# AtoVproject_16n_BOURNS_V1_2NL.net
KiCad netlist of a schematic drawn in EAGLE
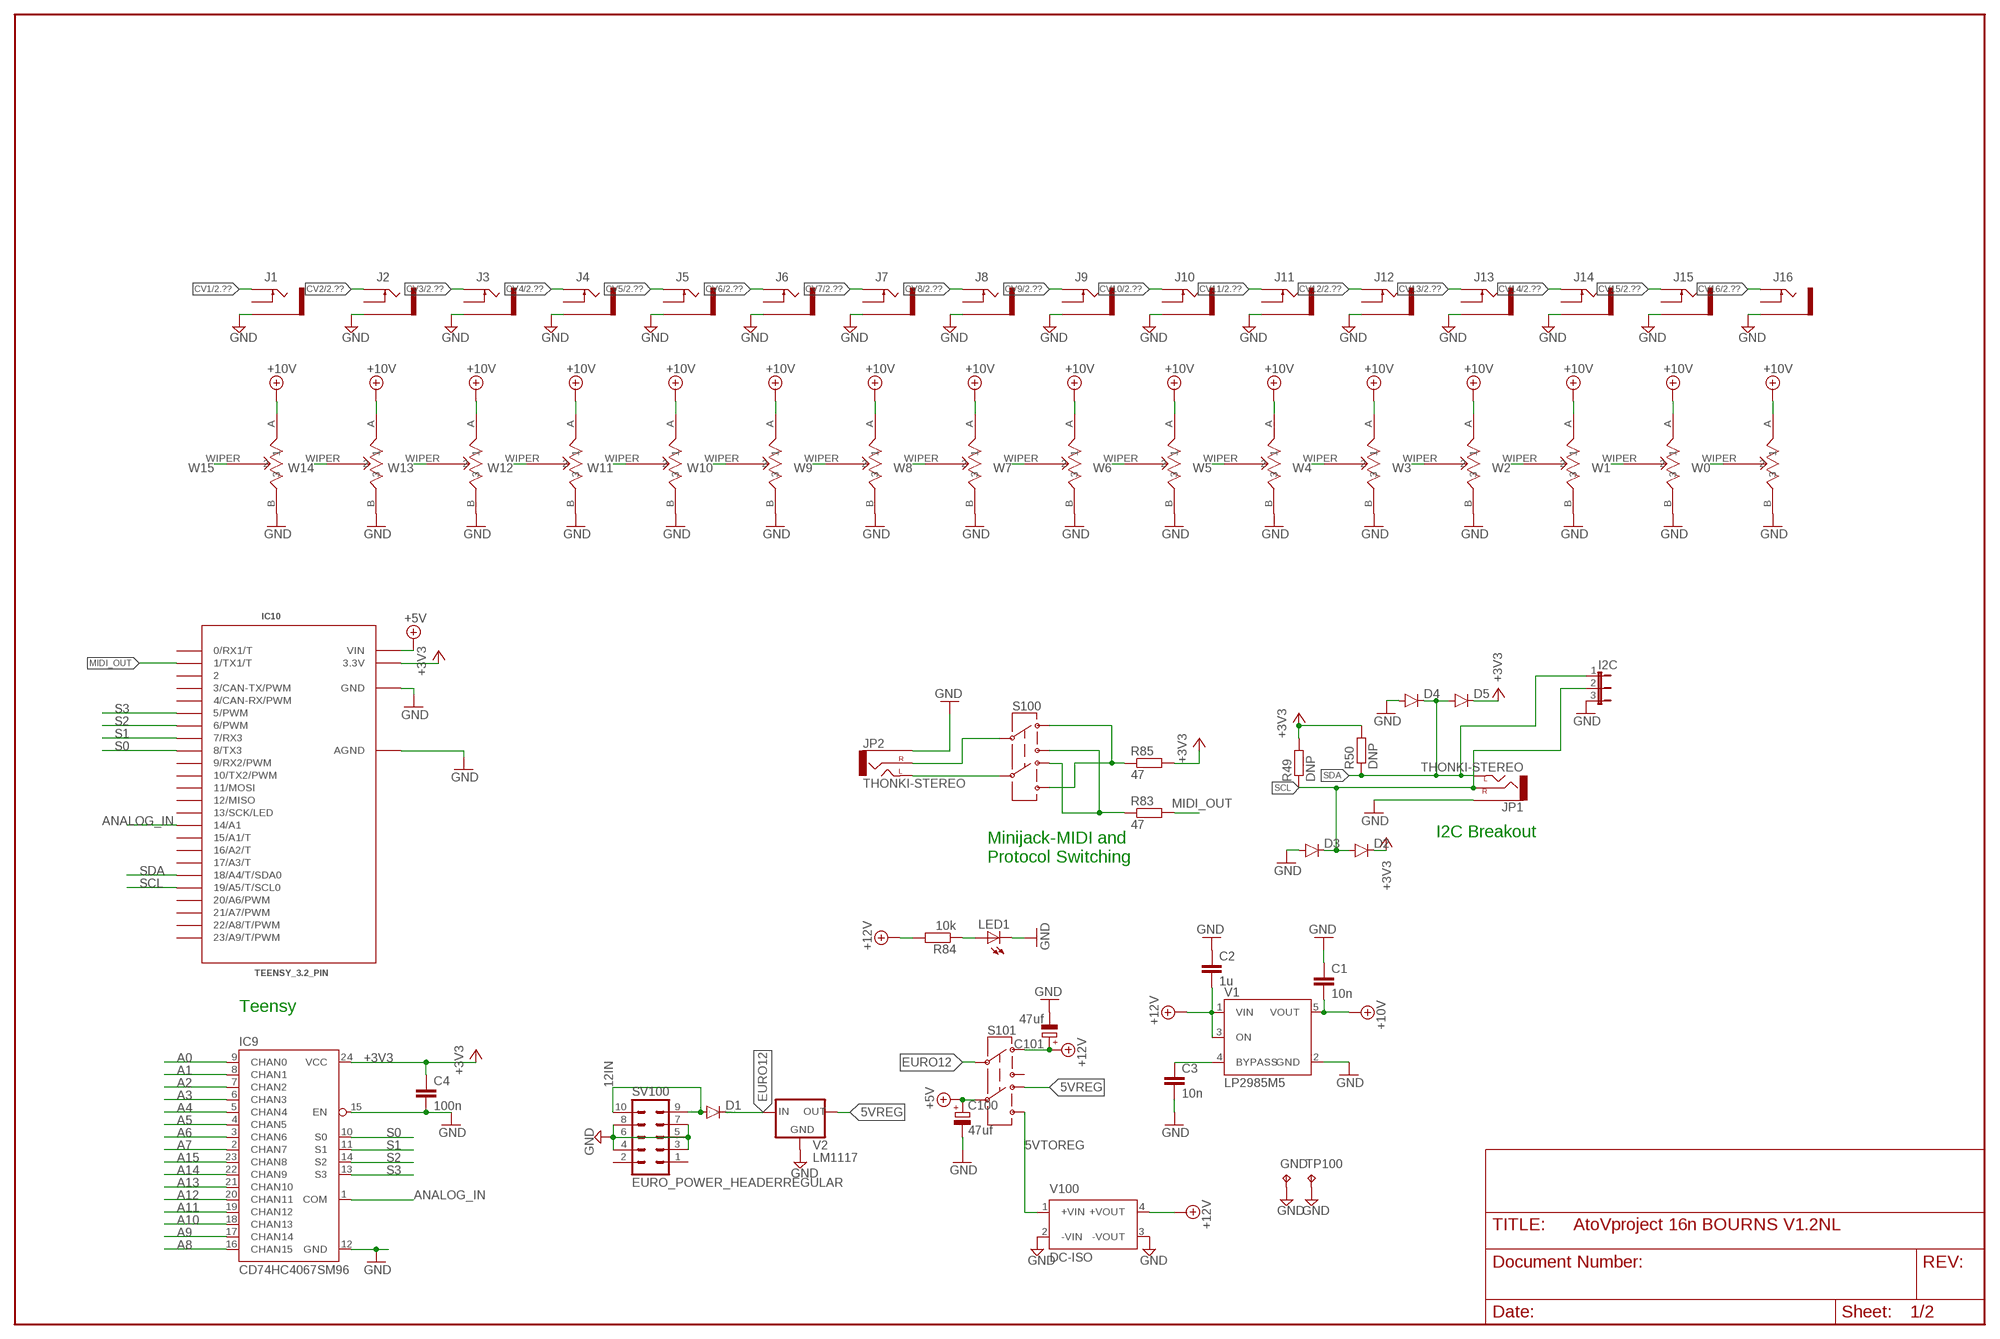
[diagram p0: schematic, sheet 1]
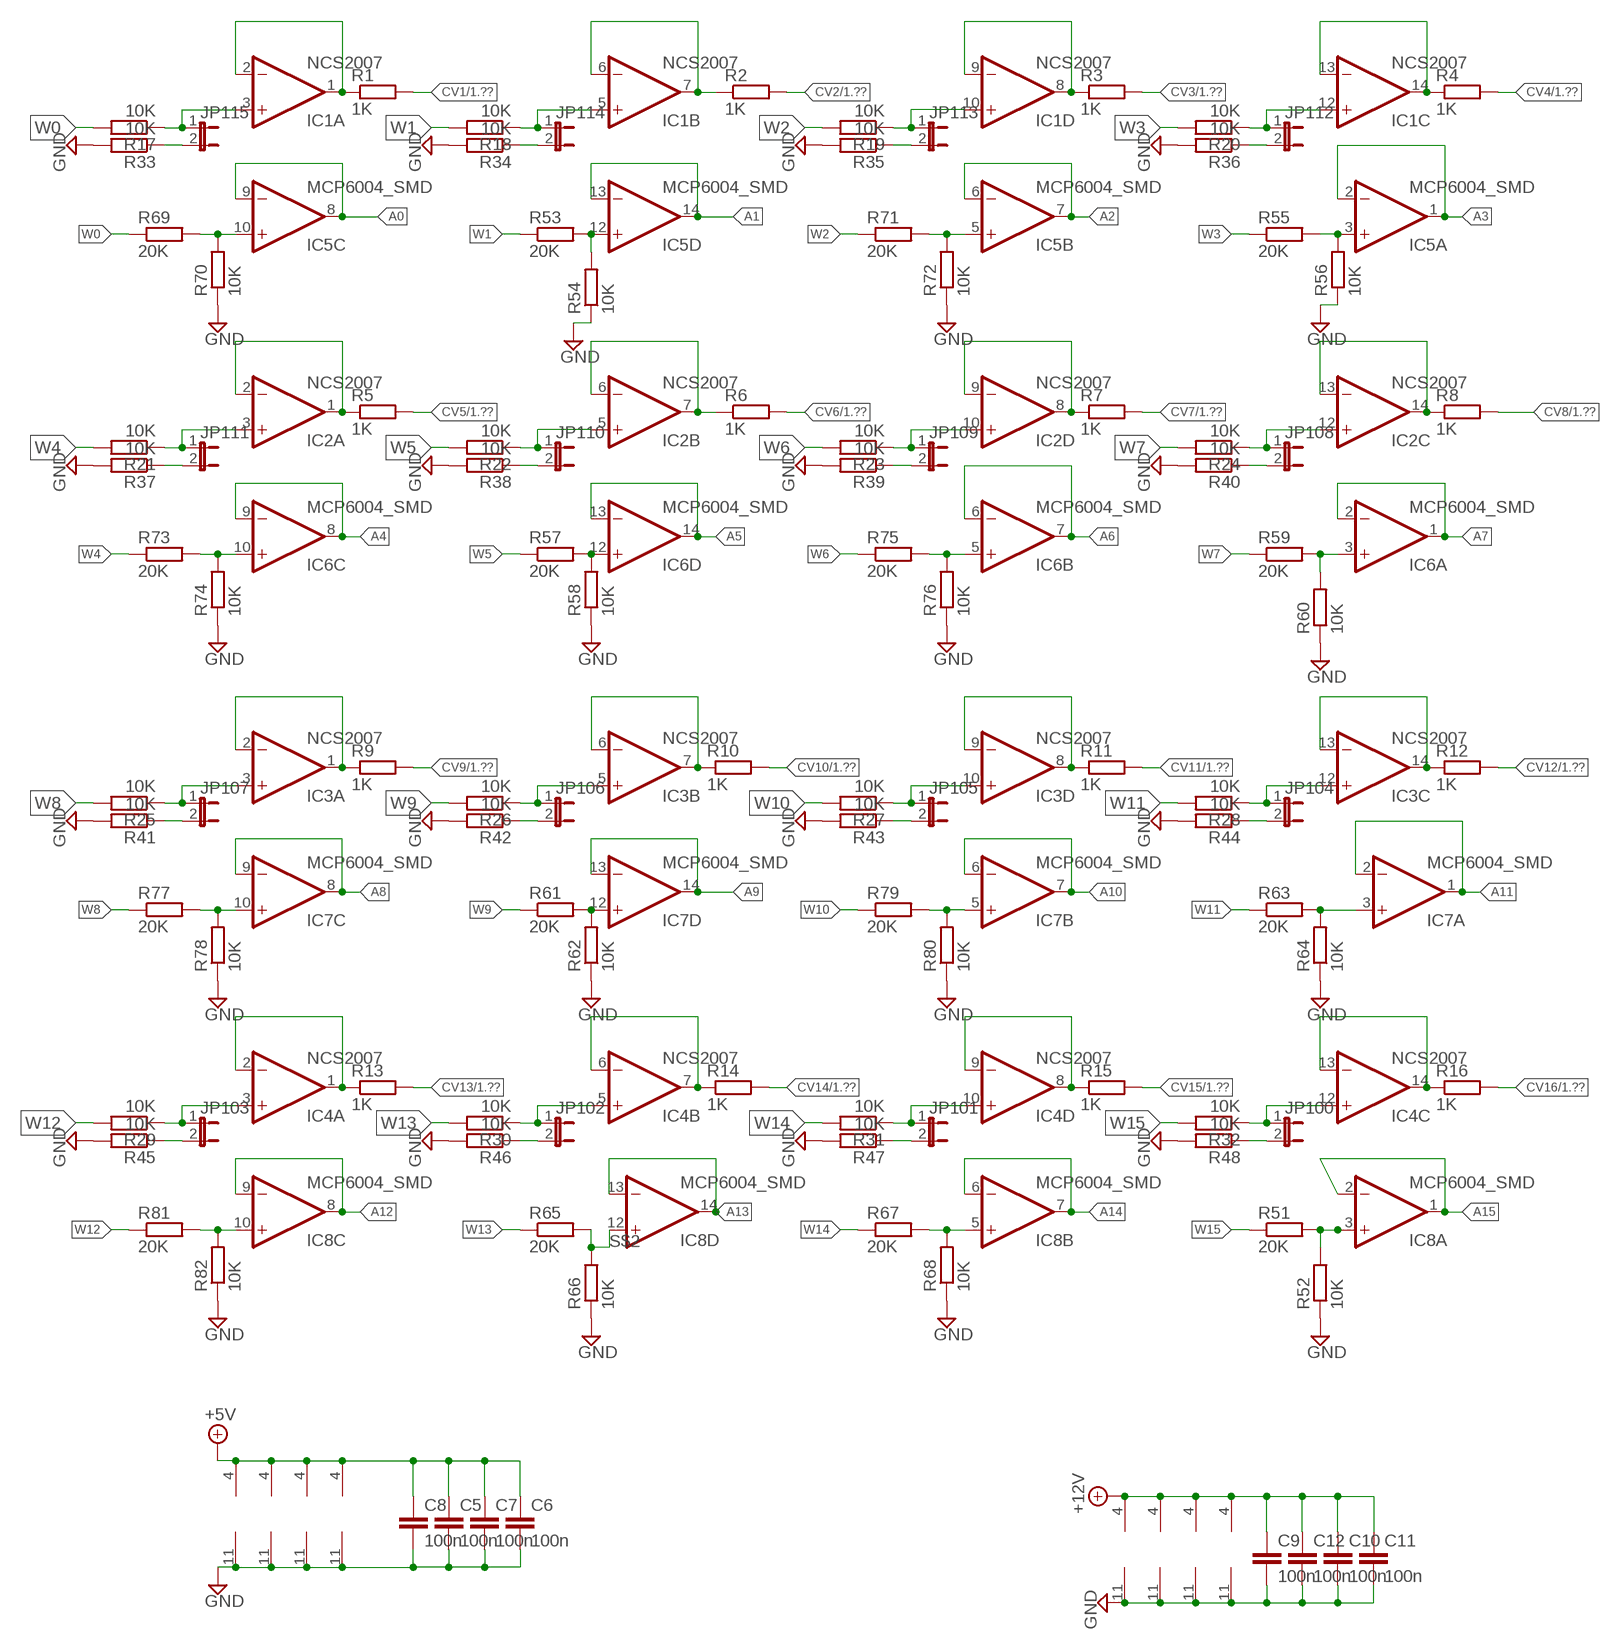
[diagram p1: schematic, sheet 2]

(export (version "E")
  (design (tool "Eeschema 10.0.6"))
  (components
    (comp (ref "C5")
      (value "100n")
      (footprint "eagle-import:C0805")
      (libsource (lib "eagle-import") (part "C-EUC0805"))
    )
    (comp (ref "C6")
      (value "100n")
      (footprint "eagle-import:C0805")
      (libsource (lib "eagle-import") (part "C-EUC0805"))
    )
    (comp (ref "C7")
      (value "100n")
      (footprint "eagle-import:C0805")
      (libsource (lib "eagle-import") (part "C-EUC0805"))
    )
    (comp (ref "C8")
      (value "100n")
      (footprint "eagle-import:C0805")
      (libsource (lib "eagle-import") (part "C-EUC0805"))
    )
    (comp (ref "C9")
      (value "100n")
      (footprint "eagle-import:C0805")
      (libsource (lib "eagle-import") (part "C-EUC0805"))
    )
    (comp (ref "C10")
      (value "100n")
      (footprint "eagle-import:C0805")
      (libsource (lib "eagle-import") (part "C-EUC0805"))
    )
    (comp (ref "C11")
      (value "100n")
      (footprint "eagle-import:C0805")
      (libsource (lib "eagle-import") (part "C-EUC0805"))
    )
    (comp (ref "C12")
      (value "100n")
      (footprint "eagle-import:C0805")
      (libsource (lib "eagle-import") (part "C-EUC0805"))
    )
    (comp (ref "IC1")
      (value "NCS2007")
      (footprint "eagle-import:SO14")
      (libsource (lib "eagle-import") (part "TL074"))
    )
    (comp (ref "IC2")
      (value "NCS2007")
      (footprint "eagle-import:SO14")
      (libsource (lib "eagle-import") (part "TL074"))
    )
    (comp (ref "IC3")
      (value "NCS2007")
      (footprint "eagle-import:SO14")
      (libsource (lib "eagle-import") (part "TL074"))
    )
    (comp (ref "IC4")
      (value "NCS2007")
      (footprint "eagle-import:SO14")
      (libsource (lib "eagle-import") (part "TL074"))
    )
    (comp (ref "IC5")
      (value "MCP6004_SMD")
      (footprint "eagle-import:SO14")
      (libsource (lib "eagle-import") (part "MCP6004_SMD"))
    )
    (comp (ref "IC6")
      (value "MCP6004_SMD")
      (footprint "eagle-import:SO14")
      (libsource (lib "eagle-import") (part "MCP6004_SMD"))
    )
    (comp (ref "IC7")
      (value "MCP6004_SMD")
      (footprint "eagle-import:SO14")
      (libsource (lib "eagle-import") (part "MCP6004_SMD"))
    )
    (comp (ref "IC8")
      (value "MCP6004_SMD")
      (footprint "eagle-import:SO14")
      (libsource (lib "eagle-import") (part "MCP6004_SMD"))
    )
    (comp (ref "JP100")
      (value "JP1E3D")
      (footprint "eagle-import:1X02")
      (libsource (lib "eagle-import") (part "JP1E3D"))
    )
    (comp (ref "JP101")
      (value "JP1E3D")
      (footprint "eagle-import:1X02")
      (libsource (lib "eagle-import") (part "JP1E3D"))
    )
    (comp (ref "JP102")
      (value "JP1E3D")
      (footprint "eagle-import:1X02")
      (libsource (lib "eagle-import") (part "JP1E3D"))
    )
    (comp (ref "JP103")
      (value "JP1E3D")
      (footprint "eagle-import:1X02")
      (libsource (lib "eagle-import") (part "JP1E3D"))
    )
    (comp (ref "JP104")
      (value "JP1E3D")
      (footprint "eagle-import:1X02")
      (libsource (lib "eagle-import") (part "JP1E3D"))
    )
    (comp (ref "JP105")
      (value "JP1E3D")
      (footprint "eagle-import:1X02")
      (libsource (lib "eagle-import") (part "JP1E3D"))
    )
    (comp (ref "JP106")
      (value "JP1E3D")
      (footprint "eagle-import:1X02")
      (libsource (lib "eagle-import") (part "JP1E3D"))
    )
    (comp (ref "JP107")
      (value "JP1E3D")
      (footprint "eagle-import:1X02")
      (libsource (lib "eagle-import") (part "JP1E3D"))
    )
    (comp (ref "JP108")
      (value "JP1E3D")
      (footprint "eagle-import:1X02")
      (libsource (lib "eagle-import") (part "JP1E3D"))
    )
    (comp (ref "JP109")
      (value "JP1E3D")
      (footprint "eagle-import:1X02")
      (libsource (lib "eagle-import") (part "JP1E3D"))
    )
    (comp (ref "JP110")
      (value "JP1E3D")
      (footprint "eagle-import:1X02")
      (libsource (lib "eagle-import") (part "JP1E3D"))
    )
    (comp (ref "JP111")
      (value "JP1E3D")
      (footprint "eagle-import:1X02")
      (libsource (lib "eagle-import") (part "JP1E3D"))
    )
    (comp (ref "JP112")
      (value "JP1E3D")
      (footprint "eagle-import:1X02")
      (libsource (lib "eagle-import") (part "JP1E3D"))
    )
    (comp (ref "JP113")
      (value "JP1E3D")
      (footprint "eagle-import:1X02")
      (libsource (lib "eagle-import") (part "JP1E3D"))
    )
    (comp (ref "JP114")
      (value "JP1E3D")
      (footprint "eagle-import:1X02")
      (libsource (lib "eagle-import") (part "JP1E3D"))
    )
    (comp (ref "JP115")
      (value "JP1E3D")
      (footprint "eagle-import:1X02")
      (libsource (lib "eagle-import") (part "JP1E3D"))
    )
    (comp (ref "R1")
      (value "1K")
      (footprint "eagle-import:R0805")
      (libsource (lib "eagle-import") (part "R-EU_R0805"))
    )
    (comp (ref "R2")
      (value "1K")
      (footprint "eagle-import:R0805")
      (libsource (lib "eagle-import") (part "R-EU_R0805"))
    )
    (comp (ref "R3")
      (value "1K")
      (footprint "eagle-import:R0805")
      (libsource (lib "eagle-import") (part "R-EU_R0805"))
    )
    (comp (ref "R4")
      (value "1K")
      (footprint "eagle-import:R0805")
      (libsource (lib "eagle-import") (part "R-EU_R0805"))
    )
    (comp (ref "R5")
      (value "1K")
      (footprint "eagle-import:R0805")
      (libsource (lib "eagle-import") (part "R-EU_R0805"))
    )
    (comp (ref "R6")
      (value "1K")
      (footprint "eagle-import:R0805")
      (libsource (lib "eagle-import") (part "R-EU_R0805"))
    )
    (comp (ref "R7")
      (value "1K")
      (footprint "eagle-import:R0805")
      (libsource (lib "eagle-import") (part "R-EU_R0805"))
    )
    (comp (ref "R8")
      (value "1K")
      (footprint "eagle-import:R0805")
      (libsource (lib "eagle-import") (part "R-EU_R0805"))
    )
    (comp (ref "R9")
      (value "1K")
      (footprint "eagle-import:R0805")
      (libsource (lib "eagle-import") (part "R-EU_R0805"))
    )
    (comp (ref "R10")
      (value "1K")
      (footprint "eagle-import:R0805")
      (libsource (lib "eagle-import") (part "R-EU_R0805"))
    )
    (comp (ref "R11")
      (value "1K")
      (footprint "eagle-import:R0805")
      (libsource (lib "eagle-import") (part "R-EU_R0805"))
    )
    (comp (ref "R12")
      (value "1K")
      (footprint "eagle-import:R0805")
      (libsource (lib "eagle-import") (part "R-EU_R0805"))
    )
    (comp (ref "R13")
      (value "1K")
      (footprint "eagle-import:R0805")
      (libsource (lib "eagle-import") (part "R-EU_R0805"))
    )
    (comp (ref "R14")
      (value "1K")
      (footprint "eagle-import:R0805")
      (libsource (lib "eagle-import") (part "R-EU_R0805"))
    )
    (comp (ref "R15")
      (value "1K")
      (footprint "eagle-import:R0805")
      (libsource (lib "eagle-import") (part "R-EU_R0805"))
    )
    (comp (ref "R16")
      (value "1K")
      (footprint "eagle-import:R0805")
      (libsource (lib "eagle-import") (part "R-EU_R0805"))
    )
    (comp (ref "R17")
      (value "10K")
      (footprint "eagle-import:R0805")
      (libsource (lib "eagle-import") (part "R-EU_R0805"))
    )
    (comp (ref "R18")
      (value "10K")
      (footprint "eagle-import:R0805")
      (libsource (lib "eagle-import") (part "R-EU_R0805"))
    )
    (comp (ref "R19")
      (value "10K")
      (footprint "eagle-import:R0805")
      (libsource (lib "eagle-import") (part "R-EU_R0805"))
    )
    (comp (ref "R20")
      (value "10K")
      (footprint "eagle-import:R0805")
      (libsource (lib "eagle-import") (part "R-EU_R0805"))
    )
    (comp (ref "R21")
      (value "10K")
      (footprint "eagle-import:R0805")
      (libsource (lib "eagle-import") (part "R-EU_R0805"))
    )
    (comp (ref "R22")
      (value "10K")
      (footprint "eagle-import:R0805")
      (libsource (lib "eagle-import") (part "R-EU_R0805"))
    )
    (comp (ref "R23")
      (value "10K")
      (footprint "eagle-import:R0805")
      (libsource (lib "eagle-import") (part "R-EU_R0805"))
    )
    (comp (ref "R24")
      (value "10K")
      (footprint "eagle-import:R0805")
      (libsource (lib "eagle-import") (part "R-EU_R0805"))
    )
    (comp (ref "R25")
      (value "10K")
      (footprint "eagle-import:R0805")
      (libsource (lib "eagle-import") (part "R-EU_R0805"))
    )
    (comp (ref "R26")
      (value "10K")
      (footprint "eagle-import:R0805")
      (libsource (lib "eagle-import") (part "R-EU_R0805"))
    )
    (comp (ref "R27")
      (value "10K")
      (footprint "eagle-import:R0805")
      (libsource (lib "eagle-import") (part "R-EU_R0805"))
    )
    (comp (ref "R28")
      (value "10K")
      (footprint "eagle-import:R0805")
      (libsource (lib "eagle-import") (part "R-EU_R0805"))
    )
    (comp (ref "R29")
      (value "10K")
      (footprint "eagle-import:R0805")
      (libsource (lib "eagle-import") (part "R-EU_R0805"))
    )
    (comp (ref "R30")
      (value "10K")
      (footprint "eagle-import:R0805")
      (libsource (lib "eagle-import") (part "R-EU_R0805"))
    )
    (comp (ref "R31")
      (value "10K")
      (footprint "eagle-import:R0805")
      (libsource (lib "eagle-import") (part "R-EU_R0805"))
    )
    (comp (ref "R32")
      (value "10K")
      (footprint "eagle-import:R0805")
      (libsource (lib "eagle-import") (part "R-EU_R0805"))
    )
    (comp (ref "R33")
      (value "10K")
      (footprint "eagle-import:R0805")
      (libsource (lib "eagle-import") (part "R-EU_R0805"))
    )
    (comp (ref "R34")
      (value "10K")
      (footprint "eagle-import:R0805")
      (libsource (lib "eagle-import") (part "R-EU_R0805"))
    )
    (comp (ref "R35")
      (value "10K")
      (footprint "eagle-import:R0805")
      (libsource (lib "eagle-import") (part "R-EU_R0805"))
    )
    (comp (ref "R36")
      (value "10K")
      (footprint "eagle-import:R0805")
      (libsource (lib "eagle-import") (part "R-EU_R0805"))
    )
    (comp (ref "R37")
      (value "10K")
      (footprint "eagle-import:R0805")
      (libsource (lib "eagle-import") (part "R-EU_R0805"))
    )
    (comp (ref "R38")
      (value "10K")
      (footprint "eagle-import:R0805")
      (libsource (lib "eagle-import") (part "R-EU_R0805"))
    )
    (comp (ref "R39")
      (value "10K")
      (footprint "eagle-import:R0805")
      (libsource (lib "eagle-import") (part "R-EU_R0805"))
    )
    (comp (ref "R40")
      (value "10K")
      (footprint "eagle-import:R0805")
      (libsource (lib "eagle-import") (part "R-EU_R0805"))
    )
    (comp (ref "R41")
      (value "10K")
      (footprint "eagle-import:R0805")
      (libsource (lib "eagle-import") (part "R-EU_R0805"))
    )
    (comp (ref "R42")
      (value "10K")
      (footprint "eagle-import:R0805")
      (libsource (lib "eagle-import") (part "R-EU_R0805"))
    )
    (comp (ref "R43")
      (value "10K")
      (footprint "eagle-import:R0805")
      (libsource (lib "eagle-import") (part "R-EU_R0805"))
    )
    (comp (ref "R44")
      (value "10K")
      (footprint "eagle-import:R0805")
      (libsource (lib "eagle-import") (part "R-EU_R0805"))
    )
    (comp (ref "R45")
      (value "10K")
      (footprint "eagle-import:R0805")
      (libsource (lib "eagle-import") (part "R-EU_R0805"))
    )
    (comp (ref "R46")
      (value "10K")
      (footprint "eagle-import:R0805")
      (libsource (lib "eagle-import") (part "R-EU_R0805"))
    )
    (comp (ref "R47")
      (value "10K")
      (footprint "eagle-import:R0805")
      (libsource (lib "eagle-import") (part "R-EU_R0805"))
    )
    (comp (ref "R48")
      (value "10K")
      (footprint "eagle-import:R0805")
      (libsource (lib "eagle-import") (part "R-EU_R0805"))
    )
    (comp (ref "R51")
      (value "20K")
      (footprint "eagle-import:R0805")
      (libsource (lib "eagle-import") (part "R-EU_R0805"))
    )
    (comp (ref "R52")
      (value "10K")
      (footprint "eagle-import:R0805")
      (libsource (lib "eagle-import") (part "R-EU_R0805"))
    )
    (comp (ref "R53")
      (value "20K")
      (footprint "eagle-import:R0805")
      (libsource (lib "eagle-import") (part "R-EU_R0805"))
    )
    (comp (ref "R54")
      (value "10K")
      (footprint "eagle-import:R0805")
      (libsource (lib "eagle-import") (part "R-EU_R0805"))
    )
    (comp (ref "R55")
      (value "20K")
      (footprint "eagle-import:R0805")
      (libsource (lib "eagle-import") (part "R-EU_R0805"))
    )
    (comp (ref "R56")
      (value "10K")
      (footprint "eagle-import:R0805")
      (libsource (lib "eagle-import") (part "R-EU_R0805"))
    )
    (comp (ref "R57")
      (value "20K")
      (footprint "eagle-import:R0805")
      (libsource (lib "eagle-import") (part "R-EU_R0805"))
    )
    (comp (ref "R58")
      (value "10K")
      (footprint "eagle-import:R0805")
      (libsource (lib "eagle-import") (part "R-EU_R0805"))
    )
    (comp (ref "R59")
      (value "20K")
      (footprint "eagle-import:R0805")
      (libsource (lib "eagle-import") (part "R-EU_R0805"))
    )
    (comp (ref "R60")
      (value "10K")
      (footprint "eagle-import:R0805")
      (libsource (lib "eagle-import") (part "R-EU_R0805"))
    )
    (comp (ref "R61")
      (value "20K")
      (footprint "eagle-import:R0805")
      (libsource (lib "eagle-import") (part "R-EU_R0805"))
    )
    (comp (ref "R62")
      (value "10K")
      (footprint "eagle-import:R0805")
      (libsource (lib "eagle-import") (part "R-EU_R0805"))
    )
    (comp (ref "R63")
      (value "20K")
      (footprint "eagle-import:R0805")
      (libsource (lib "eagle-import") (part "R-EU_R0805"))
    )
    (comp (ref "R64")
      (value "10K")
      (footprint "eagle-import:R0805")
      (libsource (lib "eagle-import") (part "R-EU_R0805"))
    )
    (comp (ref "R65")
      (value "20K")
      (footprint "eagle-import:R0805")
      (libsource (lib "eagle-import") (part "R-EU_R0805"))
    )
    (comp (ref "R66")
      (value "10K")
      (footprint "eagle-import:R0805")
      (libsource (lib "eagle-import") (part "R-EU_R0805"))
    )
    (comp (ref "R67")
      (value "20K")
      (footprint "eagle-import:R0805")
      (libsource (lib "eagle-import") (part "R-EU_R0805"))
    )
    (comp (ref "R68")
      (value "10K")
      (footprint "eagle-import:R0805")
      (libsource (lib "eagle-import") (part "R-EU_R0805"))
    )
    (comp (ref "R69")
      (value "20K")
      (footprint "eagle-import:R0805")
      (libsource (lib "eagle-import") (part "R-EU_R0805"))
    )
    (comp (ref "R70")
      (value "10K")
      (footprint "eagle-import:R0805")
      (libsource (lib "eagle-import") (part "R-EU_R0805"))
    )
    (comp (ref "R71")
      (value "20K")
      (footprint "eagle-import:R0805")
      (libsource (lib "eagle-import") (part "R-EU_R0805"))
    )
    (comp (ref "R72")
      (value "10K")
      (footprint "eagle-import:R0805")
      (libsource (lib "eagle-import") (part "R-EU_R0805"))
    )
    (comp (ref "R73")
      (value "20K")
      (footprint "eagle-import:R0805")
      (libsource (lib "eagle-import") (part "R-EU_R0805"))
    )
    (comp (ref "R74")
      (value "10K")
      (footprint "eagle-import:R0805")
      (libsource (lib "eagle-import") (part "R-EU_R0805"))
    )
    (comp (ref "R75")
      (value "20K")
      (footprint "eagle-import:R0805")
      (libsource (lib "eagle-import") (part "R-EU_R0805"))
    )
    (comp (ref "R76")
      (value "10K")
      (footprint "eagle-import:R0805")
      (libsource (lib "eagle-import") (part "R-EU_R0805"))
    )
    (comp (ref "R77")
      (value "20K")
      (footprint "eagle-import:R0805")
      (libsource (lib "eagle-import") (part "R-EU_R0805"))
    )
    (comp (ref "R78")
      (value "10K")
      (footprint "eagle-import:R0805")
      (libsource (lib "eagle-import") (part "R-EU_R0805"))
    )
    (comp (ref "R79")
      (value "20K")
      (footprint "eagle-import:R0805")
      (libsource (lib "eagle-import") (part "R-EU_R0805"))
    )
    (comp (ref "R80")
      (value "10K")
      (footprint "eagle-import:R0805")
      (libsource (lib "eagle-import") (part "R-EU_R0805"))
    )
    (comp (ref "R81")
      (value "20K")
      (footprint "eagle-import:R0805")
      (libsource (lib "eagle-import") (part "R-EU_R0805"))
    )
    (comp (ref "R82")
      (value "10K")
      (footprint "eagle-import:R0805")
      (libsource (lib "eagle-import") (part "R-EU_R0805"))
    )
    (comp (ref "C1")
      (value "10n")
      (footprint "eagle-import:C0805")
      (libsource (lib "eagle-import") (part "C-EUC0805"))
    )
    (comp (ref "C2")
      (value "1u")
      (footprint "eagle-import:C0805")
      (libsource (lib "eagle-import") (part "C-EUC0805"))
    )
    (comp (ref "C3")
      (value "10n")
      (footprint "eagle-import:C0805")
      (libsource (lib "eagle-import") (part "C-EUC0805"))
    )
    (comp (ref "C4")
      (value "100n")
      (footprint "eagle-import:C0805")
      (libsource (lib "eagle-import") (part "C-EUC0805"))
    )
    (comp (ref "C100")
      (value "47uf")
      (footprint "eagle-import:E2,5-6")
      (libsource (lib "eagle-import") (part "CPOL-EUE2.5-6"))
    )
    (comp (ref "C101")
      (value "47uf")
      (footprint "eagle-import:E2,5-6")
      (libsource (lib "eagle-import") (part "CPOL-EUE2.5-6"))
    )
    (comp (ref "D1")
      (value "DIODE-SOD123")
      (footprint "eagle-import:SOD123")
      (libsource (lib "eagle-import") (part "DIODE-SOD123"))
    )
    (comp (ref "D2")
      (value "DIODESOD123")
      (footprint "eagle-import:SOD-123")
      (libsource (lib "eagle-import") (part "DIODESOD123"))
    )
    (comp (ref "D3")
      (value "DIODESOD123")
      (footprint "eagle-import:SOD-123")
      (libsource (lib "eagle-import") (part "DIODESOD123"))
    )
    (comp (ref "D4")
      (value "DIODESOD123")
      (footprint "eagle-import:SOD-123")
      (libsource (lib "eagle-import") (part "DIODESOD123"))
    )
    (comp (ref "D5")
      (value "DIODESOD123")
      (footprint "eagle-import:SOD-123")
      (libsource (lib "eagle-import") (part "DIODESOD123"))
    )
    (comp (ref "GND")
      (value "TPPAD1-17")
      (footprint "eagle-import:P1-17")
      (libsource (lib "eagle-import") (part "TPPAD1-17"))
    )
    (comp (ref "I2C")
      (value "JP2E")
      (footprint "eagle-import:JP2")
      (libsource (lib "eagle-import") (part "JP2E"))
    )
    (comp (ref "IC9")
      (value "CD74HC4067SM96")
      (footprint "eagle-import:SOIC127P1030X265-24")
      (libsource (lib "eagle-import") (part "744067SO24"))
    )
    (comp (ref "IC10")
      (value "TEENSY_3.2_PIN")
      (footprint "eagle-import:TEENSY_3_AND_LC_SERIES_BOARDS_V1.4_TEENSY_3.0-3.2&LC_DIL")
      (libsource (lib "eagle-import") (part "TEENSY_3.2_PIN"))
    )
    (comp (ref "J1")
      (value "THONKICONN")
      (footprint "eagle-import:WQP-PJ301M-12JACK-BANANA")
      (libsource (lib "eagle-import") (part "THONKICONN"))
    )
    (comp (ref "J2")
      (value "THONKICONN")
      (footprint "eagle-import:WQP-PJ301M-12JACK-BANANA")
      (libsource (lib "eagle-import") (part "THONKICONN"))
    )
    (comp (ref "J3")
      (value "THONKICONN")
      (footprint "eagle-import:WQP-PJ301M-12JACK-BANANA")
      (libsource (lib "eagle-import") (part "THONKICONN"))
    )
    (comp (ref "J4")
      (value "THONKICONN")
      (footprint "eagle-import:WQP-PJ301M-12JACK-BANANA")
      (libsource (lib "eagle-import") (part "THONKICONN"))
    )
    (comp (ref "J5")
      (value "THONKICONN")
      (footprint "eagle-import:WQP-PJ301M-12JACK-BANANA")
      (libsource (lib "eagle-import") (part "THONKICONN"))
    )
    (comp (ref "J6")
      (value "THONKICONN")
      (footprint "eagle-import:WQP-PJ301M-12JACK-BANANA")
      (libsource (lib "eagle-import") (part "THONKICONN"))
    )
    (comp (ref "J7")
      (value "THONKICONN")
      (footprint "eagle-import:WQP-PJ301M-12JACK-BANANA")
      (libsource (lib "eagle-import") (part "THONKICONN"))
    )
    (comp (ref "J8")
      (value "THONKICONN")
      (footprint "eagle-import:WQP-PJ301M-12JACK-BANANA")
      (libsource (lib "eagle-import") (part "THONKICONN"))
    )
    (comp (ref "J9")
      (value "THONKICONN")
      (footprint "eagle-import:WQP-PJ301M-12JACK-BANANA")
      (libsource (lib "eagle-import") (part "THONKICONN"))
    )
    (comp (ref "J10")
      (value "THONKICONN")
      (footprint "eagle-import:WQP-PJ301M-12JACK-BANANA")
      (libsource (lib "eagle-import") (part "THONKICONN"))
    )
    (comp (ref "J11")
      (value "THONKICONN")
      (footprint "eagle-import:WQP-PJ301M-12JACK-BANANA")
      (libsource (lib "eagle-import") (part "THONKICONN"))
    )
    (comp (ref "J12")
      (value "THONKICONN")
      (footprint "eagle-import:WQP-PJ301M-12JACK-BANANA")
      (libsource (lib "eagle-import") (part "THONKICONN"))
    )
    (comp (ref "J13")
      (value "THONKICONN")
      (footprint "eagle-import:WQP-PJ301M-12JACK-BANANA")
      (libsource (lib "eagle-import") (part "THONKICONN"))
    )
    (comp (ref "J14")
      (value "THONKICONN")
      (footprint "eagle-import:WQP-PJ301M-12JACK-BANANA")
      (libsource (lib "eagle-import") (part "THONKICONN"))
    )
    (comp (ref "J15")
      (value "THONKICONN")
      (footprint "eagle-import:WQP-PJ301M-12JACK-BANANA")
      (libsource (lib "eagle-import") (part "THONKICONN"))
    )
    (comp (ref "J16")
      (value "THONKICONN")
      (footprint "eagle-import:WQP-PJ301M-12JACK-BANANA")
      (libsource (lib "eagle-import") (part "THONKICONN"))
    )
    (comp (ref "JP1")
      (value "THONKI-STEREO")
      (footprint "eagle-import:WQP-PJ366ST_JACK")
      (libsource (lib "eagle-import") (part "THONKI-STEREO"))
    )
    (comp (ref "JP2")
      (value "THONKI-STEREO")
      (footprint "eagle-import:WQP-PJ366ST_JACK")
      (libsource (lib "eagle-import") (part "THONKI-STEREO"))
    )
    (comp (ref "LED1")
      (value "LED")
      (footprint "eagle-import:LED3MM")
      (libsource (lib "eagle-import") (part "LED"))
    )
    (comp (ref "R49")
      (value "DNP")
      (footprint "eagle-import:R0805")
      (libsource (lib "eagle-import") (part "R-EU_R0805"))
    )
    (comp (ref "R50")
      (value "DNP")
      (footprint "eagle-import:R0805")
      (libsource (lib "eagle-import") (part "R-EU_R0805"))
    )
    (comp (ref "R83")
      (value "47")
      (footprint "eagle-import:R0805")
      (libsource (lib "eagle-import") (part "R-EU_R0805"))
    )
    (comp (ref "R84")
      (value "10k")
      (footprint "eagle-import:R0805")
      (libsource (lib "eagle-import") (part "R-EU_R0805"))
    )
    (comp (ref "R85")
      (value "47")
      (footprint "eagle-import:R0805")
      (libsource (lib "eagle-import") (part "R-EU_R0805"))
    )
    (comp (ref "S100")
      (value "SWITCH-DPDTEG2211")
      (footprint "eagle-import:EG2211")
      (libsource (lib "eagle-import") (part "SWITCH-DPDTEG2211"))
    )
    (comp (ref "S101")
      (value "SWITCH-DPDTEG2211")
      (footprint "eagle-import:EG2211")
      (libsource (lib "eagle-import") (part "SWITCH-DPDTEG2211"))
    )
    (comp (ref "SV100")
      (value "EURO_POWER_HEADERREGULAR")
      (footprint "eagle-import:EURO_POWER_HEADER")
      (libsource (lib "eagle-import") (part "EURO_POWER_HEADERREGULAR"))
    )
    (comp (ref "TP100")
      (value "TPPAD1-17")
      (footprint "eagle-import:P1-17")
      (libsource (lib "eagle-import") (part "TPPAD1-17"))
    )
    (comp (ref "U$1")
      (value "SLIDERSBOURNS-60MM")
      (footprint "eagle-import:SLIDEPOT-75")
      (libsource (lib "eagle-import") (part "SLIDERSBOURNS-60MM"))
    )
    (comp (ref "U$2")
      (value "SLIDERSBOURNS-60MM")
      (footprint "eagle-import:SLIDEPOT-75")
      (libsource (lib "eagle-import") (part "SLIDERSBOURNS-60MM"))
    )
    (comp (ref "U$3")
      (value "SLIDERSBOURNS-60MM")
      (footprint "eagle-import:SLIDEPOT-75")
      (libsource (lib "eagle-import") (part "SLIDERSBOURNS-60MM"))
    )
    (comp (ref "U$4")
      (value "SLIDERSBOURNS-60MM")
      (footprint "eagle-import:SLIDEPOT-75")
      (libsource (lib "eagle-import") (part "SLIDERSBOURNS-60MM"))
    )
    (comp (ref "U$5")
      (value "SLIDERSBOURNS-60MM")
      (footprint "eagle-import:SLIDEPOT-75")
      (libsource (lib "eagle-import") (part "SLIDERSBOURNS-60MM"))
    )
    (comp (ref "U$6")
      (value "SLIDERSBOURNS-60MM")
      (footprint "eagle-import:SLIDEPOT-75")
      (libsource (lib "eagle-import") (part "SLIDERSBOURNS-60MM"))
    )
    (comp (ref "U$7")
      (value "SLIDERSBOURNS-60MM")
      (footprint "eagle-import:SLIDEPOT-75")
      (libsource (lib "eagle-import") (part "SLIDERSBOURNS-60MM"))
    )
    (comp (ref "U$8")
      (value "SLIDERSBOURNS-60MM")
      (footprint "eagle-import:SLIDEPOT-75")
      (libsource (lib "eagle-import") (part "SLIDERSBOURNS-60MM"))
    )
    (comp (ref "U$9")
      (value "SLIDERSBOURNS-60MM")
      (footprint "eagle-import:SLIDEPOT-75")
      (libsource (lib "eagle-import") (part "SLIDERSBOURNS-60MM"))
    )
    (comp (ref "U$10")
      (value "SLIDERSBOURNS-60MM")
      (footprint "eagle-import:SLIDEPOT-75")
      (libsource (lib "eagle-import") (part "SLIDERSBOURNS-60MM"))
    )
    (comp (ref "U$11")
      (value "SLIDERSBOURNS-60MM")
      (footprint "eagle-import:SLIDEPOT-75")
      (libsource (lib "eagle-import") (part "SLIDERSBOURNS-60MM"))
    )
    (comp (ref "U$12")
      (value "SLIDERSBOURNS-60MM")
      (footprint "eagle-import:SLIDEPOT-75")
      (libsource (lib "eagle-import") (part "SLIDERSBOURNS-60MM"))
    )
    (comp (ref "U$13")
      (value "SLIDERSBOURNS-60MM")
      (footprint "eagle-import:SLIDEPOT-75")
      (libsource (lib "eagle-import") (part "SLIDERSBOURNS-60MM"))
    )
    (comp (ref "U$14")
      (value "SLIDERSBOURNS-60MM")
      (footprint "eagle-import:SLIDEPOT-75")
      (libsource (lib "eagle-import") (part "SLIDERSBOURNS-60MM"))
    )
    (comp (ref "U$15")
      (value "SLIDERSBOURNS-60MM")
      (footprint "eagle-import:SLIDEPOT-75")
      (libsource (lib "eagle-import") (part "SLIDERSBOURNS-60MM"))
    )
    (comp (ref "U$16")
      (value "SLIDERSBOURNS-60MM")
      (footprint "eagle-import:SLIDEPOT-75")
      (libsource (lib "eagle-import") (part "SLIDERSBOURNS-60MM"))
    )
    (comp (ref "V1")
      (value "LP2985M5")
      (footprint "eagle-import:SOT23-5")
      (libsource (lib "eagle-import") (part "LP2985M5"))
    )
    (comp (ref "V2")
      (value "LM1117")
      (footprint "eagle-import:SOT223")
      (libsource (lib "eagle-import") (part "LM1117"))
    )
    (comp (ref "V100")
      (value "DC-ISO")
      (footprint "eagle-import:TMA")
      (libsource (lib "eagle-import") (part "DC-ISO"))
    )
  )
  (nets
    (net (code "1") (name "+3V3") (class "Default")
      (node (ref "C4") (pin "1") (pinfunction "1_1") (pintype "passive"))
      (node (ref "D2") (pin "C") (pinfunction "C_C") (pintype "passive"))
      (node (ref "D5") (pin "C") (pinfunction "C_C") (pintype "passive"))
      (node (ref "IC10") (pin "3.3V") (pinfunction "3.3V_3.3V") (pintype "power_in"))
      (node (ref "IC9") (pin "24") (pinfunction "VCC_24") (pintype "bidirectional"))
      (node (ref "R49") (pin "2") (pinfunction "2_2") (pintype "passive"))
      (node (ref "R50") (pin "2") (pinfunction "2_2") (pintype "passive"))
      (node (ref "R85") (pin "2") (pinfunction "2_2") (pintype "passive"))
    )
    (net (code "2") (name "+5V") (class "Default")
      (node (ref "C100") (pin "+") (pinfunction "+_+") (pintype "passive"))
      (node (ref "C5") (pin "1") (pinfunction "1_1") (pintype "passive"))
      (node (ref "C6") (pin "1") (pinfunction "1_1") (pintype "passive"))
      (node (ref "C7") (pin "1") (pinfunction "1_1") (pintype "passive"))
      (node (ref "C8") (pin "1") (pinfunction "1_1") (pintype "passive"))
      (node (ref "IC10") (pin "VIN") (pinfunction "VIN_VIN") (pintype "power_in"))
      (node (ref "IC5") (pin "4") (pinfunction "V+_4") (pintype "power_in"))
      (node (ref "IC6") (pin "4") (pinfunction "V+_4") (pintype "power_in"))
      (node (ref "IC7") (pin "4") (pinfunction "V+_4") (pintype "power_in"))
      (node (ref "IC8") (pin "4") (pinfunction "V+_4") (pintype "power_in"))
      (node (ref "S101") (pin "P2") (pinfunction "5_P2") (pintype "bidirectional"))
    )
    (net (code "3") (name "+10V") (class "Default")
      (node (ref "C1") (pin "2") (pinfunction "2_2") (pintype "passive"))
      (node (ref "U$1") (pin "A") (pinfunction "1_A") (pintype "bidirectional"))
      (node (ref "U$10") (pin "A") (pinfunction "1_A") (pintype "bidirectional"))
      (node (ref "U$11") (pin "A") (pinfunction "1_A") (pintype "bidirectional"))
      (node (ref "U$12") (pin "A") (pinfunction "1_A") (pintype "bidirectional"))
      (node (ref "U$13") (pin "A") (pinfunction "1_A") (pintype "bidirectional"))
      (node (ref "U$14") (pin "A") (pinfunction "1_A") (pintype "bidirectional"))
      (node (ref "U$15") (pin "A") (pinfunction "1_A") (pintype "bidirectional"))
      (node (ref "U$16") (pin "A") (pinfunction "1_A") (pintype "bidirectional"))
      (node (ref "U$2") (pin "A") (pinfunction "1_A") (pintype "bidirectional"))
      (node (ref "U$3") (pin "A") (pinfunction "1_A") (pintype "bidirectional"))
      (node (ref "U$4") (pin "A") (pinfunction "1_A") (pintype "bidirectional"))
      (node (ref "U$5") (pin "A") (pinfunction "1_A") (pintype "bidirectional"))
      (node (ref "U$6") (pin "A") (pinfunction "1_A") (pintype "bidirectional"))
      (node (ref "U$7") (pin "A") (pinfunction "1_A") (pintype "bidirectional"))
      (node (ref "U$8") (pin "A") (pinfunction "1_A") (pintype "bidirectional"))
      (node (ref "U$9") (pin "A") (pinfunction "1_A") (pintype "bidirectional"))
      (node (ref "V1") (pin "5") (pinfunction "VOUT_5") (pintype "output"))
    )
    (net (code "4") (name "+12V") (class "Default")
      (node (ref "C10") (pin "1") (pinfunction "1_1") (pintype "passive"))
      (node (ref "C101") (pin "+") (pinfunction "+_+") (pintype "passive"))
      (node (ref "C11") (pin "1") (pinfunction "1_1") (pintype "passive"))
      (node (ref "C12") (pin "1") (pinfunction "1_1") (pintype "passive"))
      (node (ref "C2") (pin "2") (pinfunction "2_2") (pintype "passive"))
      (node (ref "C9") (pin "1") (pinfunction "1_1") (pintype "passive"))
      (node (ref "IC1") (pin "4") (pinfunction "V+_4") (pintype "power_in"))
      (node (ref "IC2") (pin "4") (pinfunction "V+_4") (pintype "power_in"))
      (node (ref "IC3") (pin "4") (pinfunction "V+_4") (pintype "power_in"))
      (node (ref "IC4") (pin "4") (pinfunction "V+_4") (pintype "power_in"))
      (node (ref "R84") (pin "2") (pinfunction "2_2") (pintype "passive"))
      (node (ref "S101") (pin "P1-TA") (pinfunction "1_P1-TA") (pintype "bidirectional"))
      (node (ref "V1") (pin "1") (pinfunction "VIN_1") (pintype "power_in"))
      (node (ref "V1") (pin "3") (pinfunction "ON_3") (pintype "input"))
      (node (ref "V100") (pin "4") (pinfunction "+VOUT_4") (pintype "passive"))
    )
    (net (code "5") (name "5VREG") (class "Default")
      (node (ref "S101") (pin "P2-TA") (pinfunction "4_P2-TA") (pintype "bidirectional"))
      (node (ref "V2") (pin "OUT") (pinfunction "OUT_OUT") (pintype "passive"))
      (node (ref "V2") (pin "TAB") (pinfunction "OUT_TAB") (pintype "passive"))
    )
    (net (code "6") (name "5VTOREG") (class "Default")
      (node (ref "S101") (pin "P2-TB") (pinfunction "6_P2-TB") (pintype "bidirectional"))
      (node (ref "V100") (pin "1") (pinfunction "+VIN_1") (pintype "passive"))
    )
    (net (code "7") (name "12IN") (class "Default")
      (node (ref "D1") (pin "A") (pinfunction "A_A") (pintype "passive"))
      (node (ref "SV100") (pin "10") (pinfunction "10_10") (pintype "passive"))
      (node (ref "SV100") (pin "9") (pinfunction "9_9") (pintype "passive"))
    )
    (net (code "8") (name "A0") (class "Default")
      (node (ref "IC5") (pin "8") (pinfunction "OUT_8") (pintype "output"))
      (node (ref "IC5") (pin "9") (pinfunction "-IN_9") (pintype "input"))
      (node (ref "IC9") (pin "9") (pinfunction "CHAN0_9") (pintype "bidirectional"))
    )
    (net (code "9") (name "A1") (class "Default")
      (node (ref "IC5") (pin "13") (pinfunction "-IN_13") (pintype "input"))
      (node (ref "IC5") (pin "14") (pinfunction "OUT_14") (pintype "output"))
      (node (ref "IC9") (pin "8") (pinfunction "CHAN1_8") (pintype "bidirectional"))
    )
    (net (code "10") (name "A2") (class "Default")
      (node (ref "IC5") (pin "6") (pinfunction "-IN_6") (pintype "input"))
      (node (ref "IC5") (pin "7") (pinfunction "OUT_7") (pintype "output"))
      (node (ref "IC9") (pin "7") (pinfunction "CHAN2_7") (pintype "bidirectional"))
    )
    (net (code "11") (name "A3") (class "Default")
      (node (ref "IC5") (pin "1") (pinfunction "OUT_1") (pintype "output"))
      (node (ref "IC5") (pin "2") (pinfunction "-IN_2") (pintype "input"))
      (node (ref "IC9") (pin "6") (pinfunction "CHAN3_6") (pintype "bidirectional"))
    )
    (net (code "12") (name "A4") (class "Default")
      (node (ref "IC6") (pin "8") (pinfunction "OUT_8") (pintype "output"))
      (node (ref "IC6") (pin "9") (pinfunction "-IN_9") (pintype "input"))
      (node (ref "IC9") (pin "5") (pinfunction "CHAN4_5") (pintype "bidirectional"))
    )
    (net (code "13") (name "A5") (class "Default")
      (node (ref "IC6") (pin "13") (pinfunction "-IN_13") (pintype "input"))
      (node (ref "IC6") (pin "14") (pinfunction "OUT_14") (pintype "output"))
      (node (ref "IC9") (pin "4") (pinfunction "CHAN5_4") (pintype "bidirectional"))
    )
    (net (code "14") (name "A6") (class "Default")
      (node (ref "IC6") (pin "6") (pinfunction "-IN_6") (pintype "input"))
      (node (ref "IC6") (pin "7") (pinfunction "OUT_7") (pintype "output"))
      (node (ref "IC9") (pin "3") (pinfunction "CHAN6_3") (pintype "bidirectional"))
    )
    (net (code "15") (name "A7") (class "Default")
      (node (ref "IC6") (pin "1") (pinfunction "OUT_1") (pintype "output"))
      (node (ref "IC6") (pin "2") (pinfunction "-IN_2") (pintype "input"))
      (node (ref "IC9") (pin "2") (pinfunction "CHAN7_2") (pintype "bidirectional"))
    )
    (net (code "16") (name "A8") (class "Default")
      (node (ref "IC7") (pin "8") (pinfunction "OUT_8") (pintype "output"))
      (node (ref "IC7") (pin "9") (pinfunction "-IN_9") (pintype "input"))
      (node (ref "IC9") (pin "16") (pinfunction "CHAN15_16") (pintype "bidirectional"))
    )
    (net (code "17") (name "A9") (class "Default")
      (node (ref "IC7") (pin "13") (pinfunction "-IN_13") (pintype "input"))
      (node (ref "IC7") (pin "14") (pinfunction "OUT_14") (pintype "output"))
      (node (ref "IC9") (pin "17") (pinfunction "CHAN14_17") (pintype "bidirectional"))
    )
    (net (code "18") (name "A10") (class "Default")
      (node (ref "IC7") (pin "6") (pinfunction "-IN_6") (pintype "input"))
      (node (ref "IC7") (pin "7") (pinfunction "OUT_7") (pintype "output"))
      (node (ref "IC9") (pin "18") (pinfunction "CHAN13_18") (pintype "bidirectional"))
    )
    (net (code "19") (name "A11") (class "Default")
      (node (ref "IC7") (pin "1") (pinfunction "OUT_1") (pintype "output"))
      (node (ref "IC7") (pin "2") (pinfunction "-IN_2") (pintype "input"))
      (node (ref "IC9") (pin "19") (pinfunction "CHAN12_19") (pintype "bidirectional"))
    )
    (net (code "20") (name "A12") (class "Default")
      (node (ref "IC8") (pin "8") (pinfunction "OUT_8") (pintype "output"))
      (node (ref "IC8") (pin "9") (pinfunction "-IN_9") (pintype "input"))
      (node (ref "IC9") (pin "20") (pinfunction "CHAN11_20") (pintype "bidirectional"))
    )
    (net (code "21") (name "A13") (class "Default")
      (node (ref "IC8") (pin "13") (pinfunction "-IN_13") (pintype "input"))
      (node (ref "IC8") (pin "14") (pinfunction "OUT_14") (pintype "output"))
      (node (ref "IC9") (pin "21") (pinfunction "CHAN10_21") (pintype "bidirectional"))
    )
    (net (code "22") (name "A14") (class "Default")
      (node (ref "IC8") (pin "6") (pinfunction "-IN_6") (pintype "input"))
      (node (ref "IC8") (pin "7") (pinfunction "OUT_7") (pintype "output"))
      (node (ref "IC9") (pin "22") (pinfunction "CHAN9_22") (pintype "bidirectional"))
    )
    (net (code "23") (name "A15") (class "Default")
      (node (ref "IC8") (pin "1") (pinfunction "OUT_1") (pintype "output"))
      (node (ref "IC8") (pin "2") (pinfunction "-IN_2") (pintype "input"))
      (node (ref "IC9") (pin "23") (pinfunction "CHAN8_23") (pintype "bidirectional"))
    )
    (net (code "24") (name "ANALOG_IN") (class "Default")
      (node (ref "IC10") (pin "14/A0") (pinfunction "14/A1_14/A0") (pintype "bidirectional"))
      (node (ref "IC9") (pin "1") (pinfunction "COM_1") (pintype "bidirectional"))
    )
    (net (code "25") (name "CV1") (class "Default")
      (node (ref "J1") (pin "P$1_TIP") (pinfunction "TIP_P$1_TIP") (pintype "passive"))
      (node (ref "R1") (pin "2") (pinfunction "2_2") (pintype "passive"))
    )
    (net (code "26") (name "CV2") (class "Default")
      (node (ref "J2") (pin "P$1_TIP") (pinfunction "TIP_P$1_TIP") (pintype "passive"))
      (node (ref "R2") (pin "2") (pinfunction "2_2") (pintype "passive"))
    )
    (net (code "27") (name "CV3") (class "Default")
      (node (ref "J3") (pin "P$1_TIP") (pinfunction "TIP_P$1_TIP") (pintype "passive"))
      (node (ref "R3") (pin "2") (pinfunction "2_2") (pintype "passive"))
    )
    (net (code "28") (name "CV4") (class "Default")
      (node (ref "J4") (pin "P$1_TIP") (pinfunction "TIP_P$1_TIP") (pintype "passive"))
      (node (ref "R4") (pin "2") (pinfunction "2_2") (pintype "passive"))
    )
    (net (code "29") (name "CV5") (class "Default")
      (node (ref "J5") (pin "P$1_TIP") (pinfunction "TIP_P$1_TIP") (pintype "passive"))
      (node (ref "R5") (pin "2") (pinfunction "2_2") (pintype "passive"))
    )
    (net (code "30") (name "CV6") (class "Default")
      (node (ref "J6") (pin "P$1_TIP") (pinfunction "TIP_P$1_TIP") (pintype "passive"))
      (node (ref "R6") (pin "2") (pinfunction "2_2") (pintype "passive"))
    )
    (net (code "31") (name "CV7") (class "Default")
      (node (ref "J7") (pin "P$1_TIP") (pinfunction "TIP_P$1_TIP") (pintype "passive"))
      (node (ref "R7") (pin "2") (pinfunction "2_2") (pintype "passive"))
    )
    (net (code "32") (name "CV8") (class "Default")
      (node (ref "J8") (pin "P$1_TIP") (pinfunction "TIP_P$1_TIP") (pintype "passive"))
      (node (ref "R8") (pin "2") (pinfunction "2_2") (pintype "passive"))
    )
    (net (code "33") (name "CV9") (class "Default")
      (node (ref "J9") (pin "P$1_TIP") (pinfunction "TIP_P$1_TIP") (pintype "passive"))
      (node (ref "R9") (pin "2") (pinfunction "2_2") (pintype "passive"))
    )
    (net (code "34") (name "CV10") (class "Default")
      (node (ref "J10") (pin "P$1_TIP") (pinfunction "TIP_P$1_TIP") (pintype "passive"))
      (node (ref "R10") (pin "2") (pinfunction "2_2") (pintype "passive"))
    )
    (net (code "35") (name "CV11") (class "Default")
      (node (ref "J11") (pin "P$1_TIP") (pinfunction "TIP_P$1_TIP") (pintype "passive"))
      (node (ref "R11") (pin "2") (pinfunction "2_2") (pintype "passive"))
    )
    (net (code "36") (name "CV12") (class "Default")
      (node (ref "J12") (pin "P$1_TIP") (pinfunction "TIP_P$1_TIP") (pintype "passive"))
      (node (ref "R12") (pin "2") (pinfunction "2_2") (pintype "passive"))
    )
    (net (code "37") (name "CV13") (class "Default")
      (node (ref "J13") (pin "P$1_TIP") (pinfunction "TIP_P$1_TIP") (pintype "passive"))
      (node (ref "R13") (pin "2") (pinfunction "2_2") (pintype "passive"))
    )
    (net (code "38") (name "CV14") (class "Default")
      (node (ref "J14") (pin "P$1_TIP") (pinfunction "TIP_P$1_TIP") (pintype "passive"))
      (node (ref "R14") (pin "2") (pinfunction "2_2") (pintype "passive"))
    )
    (net (code "39") (name "CV15") (class "Default")
      (node (ref "J15") (pin "P$1_TIP") (pinfunction "TIP_P$1_TIP") (pintype "passive"))
      (node (ref "R15") (pin "2") (pinfunction "2_2") (pintype "passive"))
    )
    (net (code "40") (name "CV16") (class "Default")
      (node (ref "J16") (pin "P$1_TIP") (pinfunction "TIP_P$1_TIP") (pintype "passive"))
      (node (ref "R16") (pin "2") (pinfunction "2_2") (pintype "passive"))
    )
    (net (code "41") (name "EURO12") (class "Default")
      (node (ref "D1") (pin "C") (pinfunction "C_C") (pintype "passive"))
      (node (ref "S101") (pin "P1") (pinfunction "2_P1") (pintype "bidirectional"))
      (node (ref "V2") (pin "IN") (pinfunction "IN_IN") (pintype "input"))
    )
    (net (code "42") (name "GND") (class "Default")
      (node (ref "C1") (pin "1") (pinfunction "1_1") (pintype "passive"))
      (node (ref "C10") (pin "2") (pinfunction "2_2") (pintype "passive"))
      (node (ref "C100") (pin "-") (pinfunction "-_-") (pintype "passive"))
      (node (ref "C101") (pin "-") (pinfunction "-_-") (pintype "passive"))
      (node (ref "C11") (pin "2") (pinfunction "2_2") (pintype "passive"))
      (node (ref "C12") (pin "2") (pinfunction "2_2") (pintype "passive"))
      (node (ref "C2") (pin "1") (pinfunction "1_1") (pintype "passive"))
      (node (ref "C3") (pin "2") (pinfunction "2_2") (pintype "passive"))
      (node (ref "C4") (pin "2") (pinfunction "2_2") (pintype "passive"))
      (node (ref "C5") (pin "2") (pinfunction "2_2") (pintype "passive"))
      (node (ref "C6") (pin "2") (pinfunction "2_2") (pintype "passive"))
      (node (ref "C7") (pin "2") (pinfunction "2_2") (pintype "passive"))
      (node (ref "C8") (pin "2") (pinfunction "2_2") (pintype "passive"))
      (node (ref "C9") (pin "2") (pinfunction "2_2") (pintype "passive"))
      (node (ref "D3") (pin "A") (pinfunction "A_A") (pintype "passive"))
      (node (ref "D4") (pin "A") (pinfunction "A_A") (pintype "passive"))
      (node (ref "GND") (pin "TP") (pinfunction "TP_TP") (pintype "input"))
      (node (ref "I2C") (pin "3") (pinfunction "3_3") (pintype "passive"))
      (node (ref "IC1") (pin "11") (pinfunction "V-_11") (pintype "power_in"))
      (node (ref "IC10") (pin "AGND") (pinfunction "AGND_AGND") (pintype "power_in"))
      (node (ref "IC10") (pin "GND") (pinfunction "GND_GND") (pintype "power_in"))
      (node (ref "IC2") (pin "11") (pinfunction "V-_11") (pintype "power_in"))
      (node (ref "IC3") (pin "11") (pinfunction "V-_11") (pintype "power_in"))
      (node (ref "IC4") (pin "11") (pinfunction "V-_11") (pintype "power_in"))
      (node (ref "IC5") (pin "11") (pinfunction "V-_11") (pintype "power_in"))
      (node (ref "IC6") (pin "11") (pinfunction "V-_11") (pintype "power_in"))
      (node (ref "IC7") (pin "11") (pinfunction "V-_11") (pintype "power_in"))
      (node (ref "IC8") (pin "11") (pinfunction "V-_11") (pintype "power_in"))
      (node (ref "IC9") (pin "12") (pinfunction "GND_12") (pintype "bidirectional"))
      (node (ref "IC9") (pin "15") (pinfunction "EN_15") (pintype "input"))
      (node (ref "J1") (pin "P$3_SLEEVE") (pinfunction "SLEEVE_P$3_SLEEVE") (pintype "passive"))
      (node (ref "J10") (pin "P$3_SLEEVE") (pinfunction "SLEEVE_P$3_SLEEVE") (pintype "passive"))
      (node (ref "J11") (pin "P$3_SLEEVE") (pinfunction "SLEEVE_P$3_SLEEVE") (pintype "passive"))
      (node (ref "J12") (pin "P$3_SLEEVE") (pinfunction "SLEEVE_P$3_SLEEVE") (pintype "passive"))
      (node (ref "J13") (pin "P$3_SLEEVE") (pinfunction "SLEEVE_P$3_SLEEVE") (pintype "passive"))
      (node (ref "J14") (pin "P$3_SLEEVE") (pinfunction "SLEEVE_P$3_SLEEVE") (pintype "passive"))
      (node (ref "J15") (pin "P$3_SLEEVE") (pinfunction "SLEEVE_P$3_SLEEVE") (pintype "passive"))
      (node (ref "J16") (pin "P$3_SLEEVE") (pinfunction "SLEEVE_P$3_SLEEVE") (pintype "passive"))
      (node (ref "J2") (pin "P$3_SLEEVE") (pinfunction "SLEEVE_P$3_SLEEVE") (pintype "passive"))
      (node (ref "J3") (pin "P$3_SLEEVE") (pinfunction "SLEEVE_P$3_SLEEVE") (pintype "passive"))
      (node (ref "J4") (pin "P$3_SLEEVE") (pinfunction "SLEEVE_P$3_SLEEVE") (pintype "passive"))
      (node (ref "J5") (pin "P$3_SLEEVE") (pinfunction "SLEEVE_P$3_SLEEVE") (pintype "passive"))
      (node (ref "J6") (pin "P$3_SLEEVE") (pinfunction "SLEEVE_P$3_SLEEVE") (pintype "passive"))
      (node (ref "J7") (pin "P$3_SLEEVE") (pinfunction "SLEEVE_P$3_SLEEVE") (pintype "passive"))
      (node (ref "J8") (pin "P$3_SLEEVE") (pinfunction "SLEEVE_P$3_SLEEVE") (pintype "passive"))
      (node (ref "J9") (pin "P$3_SLEEVE") (pinfunction "SLEEVE_P$3_SLEEVE") (pintype "passive"))
      (node (ref "JP1") (pin "P$3_SLEEVE") (pinfunction "SLEEVE_P$3_SLEEVE") (pintype "bidirectional"))
      (node (ref "JP2") (pin "P$3_SLEEVE") (pinfunction "SLEEVE_P$3_SLEEVE") (pintype "bidirectional"))
      (node (ref "LED1") (pin "K") (pinfunction "C_K") (pintype "passive"))
      (node (ref "R33") (pin "2") (pinfunction "2_2") (pintype "passive"))
      (node (ref "R34") (pin "2") (pinfunction "2_2") (pintype "passive"))
      (node (ref "R35") (pin "2") (pinfunction "2_2") (pintype "passive"))
      (node (ref "R36") (pin "2") (pinfunction "2_2") (pintype "passive"))
      (node (ref "R37") (pin "2") (pinfunction "2_2") (pintype "passive"))
      (node (ref "R38") (pin "2") (pinfunction "2_2") (pintype "passive"))
      (node (ref "R39") (pin "2") (pinfunction "2_2") (pintype "passive"))
      (node (ref "R40") (pin "2") (pinfunction "2_2") (pintype "passive"))
      (node (ref "R41") (pin "2") (pinfunction "2_2") (pintype "passive"))
      (node (ref "R42") (pin "2") (pinfunction "2_2") (pintype "passive"))
      (node (ref "R43") (pin "2") (pinfunction "2_2") (pintype "passive"))
      (node (ref "R44") (pin "2") (pinfunction "2_2") (pintype "passive"))
      (node (ref "R45") (pin "2") (pinfunction "2_2") (pintype "passive"))
      (node (ref "R46") (pin "2") (pinfunction "2_2") (pintype "passive"))
      (node (ref "R47") (pin "2") (pinfunction "2_2") (pintype "passive"))
      (node (ref "R48") (pin "2") (pinfunction "2_2") (pintype "passive"))
      (node (ref "R52") (pin "1") (pinfunction "1_1") (pintype "passive"))
      (node (ref "R54") (pin "1") (pinfunction "1_1") (pintype "passive"))
      (node (ref "R56") (pin "1") (pinfunction "1_1") (pintype "passive"))
      (node (ref "R58") (pin "1") (pinfunction "1_1") (pintype "passive"))
      (node (ref "R60") (pin "1") (pinfunction "1_1") (pintype "passive"))
      (node (ref "R62") (pin "1") (pinfunction "1_1") (pintype "passive"))
      (node (ref "R64") (pin "1") (pinfunction "1_1") (pintype "passive"))
      (node (ref "R66") (pin "1") (pinfunction "1_1") (pintype "passive"))
      (node (ref "R68") (pin "1") (pinfunction "1_1") (pintype "passive"))
      (node (ref "R70") (pin "1") (pinfunction "1_1") (pintype "passive"))
      (node (ref "R72") (pin "1") (pinfunction "1_1") (pintype "passive"))
      (node (ref "R74") (pin "1") (pinfunction "1_1") (pintype "passive"))
      (node (ref "R76") (pin "1") (pinfunction "1_1") (pintype "passive"))
      (node (ref "R78") (pin "1") (pinfunction "1_1") (pintype "passive"))
      (node (ref "R80") (pin "1") (pinfunction "1_1") (pintype "passive"))
      (node (ref "R82") (pin "1") (pinfunction "1_1") (pintype "passive"))
      (node (ref "SV100") (pin "3") (pinfunction "3_3") (pintype "passive"))
      (node (ref "SV100") (pin "4") (pinfunction "4_4") (pintype "passive"))
      (node (ref "SV100") (pin "5") (pinfunction "5_5") (pintype "passive"))
      (node (ref "SV100") (pin "6") (pinfunction "6_6") (pintype "passive"))
      (node (ref "SV100") (pin "7") (pinfunction "7_7") (pintype "passive"))
      (node (ref "SV100") (pin "8") (pinfunction "8_8") (pintype "passive"))
      (node (ref "TP100") (pin "TP") (pinfunction "TP_TP") (pintype "input"))
      (node (ref "U$1") (pin "B") (pinfunction "3_B") (pintype "bidirectional"))
      (node (ref "U$10") (pin "B") (pinfunction "3_B") (pintype "bidirectional"))
      (node (ref "U$11") (pin "B") (pinfunction "3_B") (pintype "bidirectional"))
      (node (ref "U$12") (pin "B") (pinfunction "3_B") (pintype "bidirectional"))
      (node (ref "U$13") (pin "B") (pinfunction "3_B") (pintype "bidirectional"))
      (node (ref "U$14") (pin "B") (pinfunction "3_B") (pintype "bidirectional"))
      (node (ref "U$15") (pin "B") (pinfunction "3_B") (pintype "bidirectional"))
      (node (ref "U$16") (pin "B") (pinfunction "3_B") (pintype "bidirectional"))
      (node (ref "U$2") (pin "B") (pinfunction "3_B") (pintype "bidirectional"))
      (node (ref "U$3") (pin "B") (pinfunction "3_B") (pintype "bidirectional"))
      (node (ref "U$4") (pin "B") (pinfunction "3_B") (pintype "bidirectional"))
      (node (ref "U$5") (pin "B") (pinfunction "3_B") (pintype "bidirectional"))
      (node (ref "U$6") (pin "B") (pinfunction "3_B") (pintype "bidirectional"))
      (node (ref "U$7") (pin "B") (pinfunction "3_B") (pintype "bidirectional"))
      (node (ref "U$8") (pin "B") (pinfunction "3_B") (pintype "bidirectional"))
      (node (ref "U$9") (pin "B") (pinfunction "3_B") (pintype "bidirectional"))
      (node (ref "V1") (pin "2") (pinfunction "GND_2") (pintype "power_in"))
      (node (ref "V100") (pin "2") (pinfunction "-VIN_2") (pintype "passive"))
      (node (ref "V100") (pin "3") (pinfunction "-VOUT_3") (pintype "passive"))
      (node (ref "V2") (pin "GND") (pinfunction "GND_GND") (pintype "input"))
    )
    (net (code "43") (name "MIDI_OUT") (class "Default")
      (node (ref "IC10") (pin "1") (pinfunction "1/TX1/T_1") (pintype "bidirectional"))
      (node (ref "R83") (pin "2") (pinfunction "2_2") (pintype "passive"))
    )
    (net (code "44") (name "Net-(IC1A-+IN)") (class "Default")
      (node (ref "IC1") (pin "3") (pinfunction "+IN_3") (pintype "input"))
      (node (ref "JP115") (pin "1") (pinfunction "1_1") (pintype "passive"))
      (node (ref "R17") (pin "1") (pinfunction "1_1") (pintype "passive"))
    )
    (net (code "45") (name "Net-(IC1A--IN)") (class "Default")
      (node (ref "IC1") (pin "1") (pinfunction "OUT_1") (pintype "output"))
      (node (ref "IC1") (pin "2") (pinfunction "-IN_2") (pintype "input"))
      (node (ref "R1") (pin "1") (pinfunction "1_1") (pintype "passive"))
    )
    (net (code "46") (name "Net-(IC1B-+IN)") (class "Default")
      (node (ref "IC1") (pin "5") (pinfunction "+IN_5") (pintype "input"))
      (node (ref "JP114") (pin "1") (pinfunction "1_1") (pintype "passive"))
      (node (ref "R18") (pin "1") (pinfunction "1_1") (pintype "passive"))
    )
    (net (code "47") (name "Net-(IC1B--IN)") (class "Default")
      (node (ref "IC1") (pin "6") (pinfunction "-IN_6") (pintype "input"))
      (node (ref "IC1") (pin "7") (pinfunction "OUT_7") (pintype "output"))
      (node (ref "R2") (pin "1") (pinfunction "1_1") (pintype "passive"))
    )
    (net (code "48") (name "Net-(IC1C-+IN)") (class "Default")
      (node (ref "IC1") (pin "12") (pinfunction "+IN_12") (pintype "input"))
      (node (ref "JP112") (pin "1") (pinfunction "1_1") (pintype "passive"))
      (node (ref "R20") (pin "1") (pinfunction "1_1") (pintype "passive"))
    )
    (net (code "49") (name "Net-(IC1C--IN)") (class "Default")
      (node (ref "IC1") (pin "13") (pinfunction "-IN_13") (pintype "input"))
      (node (ref "IC1") (pin "14") (pinfunction "OUT_14") (pintype "output"))
      (node (ref "R4") (pin "1") (pinfunction "1_1") (pintype "passive"))
    )
    (net (code "50") (name "Net-(IC1D-+IN)") (class "Default")
      (node (ref "IC1") (pin "10") (pinfunction "+IN_10") (pintype "input"))
      (node (ref "JP113") (pin "1") (pinfunction "1_1") (pintype "passive"))
      (node (ref "R19") (pin "1") (pinfunction "1_1") (pintype "passive"))
    )
    (net (code "51") (name "Net-(IC1D--IN)") (class "Default")
      (node (ref "IC1") (pin "8") (pinfunction "OUT_8") (pintype "output"))
      (node (ref "IC1") (pin "9") (pinfunction "-IN_9") (pintype "input"))
      (node (ref "R3") (pin "1") (pinfunction "1_1") (pintype "passive"))
    )
    (net (code "52") (name "Net-(IC2A-+IN)") (class "Default")
      (node (ref "IC2") (pin "3") (pinfunction "+IN_3") (pintype "input"))
      (node (ref "JP111") (pin "1") (pinfunction "1_1") (pintype "passive"))
      (node (ref "R21") (pin "1") (pinfunction "1_1") (pintype "passive"))
    )
    (net (code "53") (name "Net-(IC2A--IN)") (class "Default")
      (node (ref "IC2") (pin "1") (pinfunction "OUT_1") (pintype "output"))
      (node (ref "IC2") (pin "2") (pinfunction "-IN_2") (pintype "input"))
      (node (ref "R5") (pin "1") (pinfunction "1_1") (pintype "passive"))
    )
    (net (code "54") (name "Net-(IC2B-+IN)") (class "Default")
      (node (ref "IC2") (pin "5") (pinfunction "+IN_5") (pintype "input"))
      (node (ref "JP110") (pin "1") (pinfunction "1_1") (pintype "passive"))
      (node (ref "R22") (pin "1") (pinfunction "1_1") (pintype "passive"))
    )
    (net (code "55") (name "Net-(IC2B--IN)") (class "Default")
      (node (ref "IC2") (pin "6") (pinfunction "-IN_6") (pintype "input"))
      (node (ref "IC2") (pin "7") (pinfunction "OUT_7") (pintype "output"))
      (node (ref "R6") (pin "1") (pinfunction "1_1") (pintype "passive"))
    )
    (net (code "56") (name "Net-(IC2C-+IN)") (class "Default")
      (node (ref "IC2") (pin "12") (pinfunction "+IN_12") (pintype "input"))
      (node (ref "JP108") (pin "1") (pinfunction "1_1") (pintype "passive"))
      (node (ref "R24") (pin "1") (pinfunction "1_1") (pintype "passive"))
    )
    (net (code "57") (name "Net-(IC2C--IN)") (class "Default")
      (node (ref "IC2") (pin "13") (pinfunction "-IN_13") (pintype "input"))
      (node (ref "IC2") (pin "14") (pinfunction "OUT_14") (pintype "output"))
      (node (ref "R8") (pin "1") (pinfunction "1_1") (pintype "passive"))
    )
    (net (code "58") (name "Net-(IC2D-+IN)") (class "Default")
      (node (ref "IC2") (pin "10") (pinfunction "+IN_10") (pintype "input"))
      (node (ref "JP109") (pin "1") (pinfunction "1_1") (pintype "passive"))
      (node (ref "R23") (pin "1") (pinfunction "1_1") (pintype "passive"))
    )
    (net (code "59") (name "Net-(IC2D--IN)") (class "Default")
      (node (ref "IC2") (pin "8") (pinfunction "OUT_8") (pintype "output"))
      (node (ref "IC2") (pin "9") (pinfunction "-IN_9") (pintype "input"))
      (node (ref "R7") (pin "1") (pinfunction "1_1") (pintype "passive"))
    )
    (net (code "60") (name "Net-(IC3A-+IN)") (class "Default")
      (node (ref "IC3") (pin "3") (pinfunction "+IN_3") (pintype "input"))
      (node (ref "JP107") (pin "1") (pinfunction "1_1") (pintype "passive"))
      (node (ref "R25") (pin "1") (pinfunction "1_1") (pintype "passive"))
    )
    (net (code "61") (name "Net-(IC3A--IN)") (class "Default")
      (node (ref "IC3") (pin "1") (pinfunction "OUT_1") (pintype "output"))
      (node (ref "IC3") (pin "2") (pinfunction "-IN_2") (pintype "input"))
      (node (ref "R9") (pin "1") (pinfunction "1_1") (pintype "passive"))
    )
    (net (code "62") (name "Net-(IC3B-+IN)") (class "Default")
      (node (ref "IC3") (pin "5") (pinfunction "+IN_5") (pintype "input"))
      (node (ref "JP106") (pin "1") (pinfunction "1_1") (pintype "passive"))
      (node (ref "R26") (pin "1") (pinfunction "1_1") (pintype "passive"))
    )
    (net (code "63") (name "Net-(IC3B--IN)") (class "Default")
      (node (ref "IC3") (pin "6") (pinfunction "-IN_6") (pintype "input"))
      (node (ref "IC3") (pin "7") (pinfunction "OUT_7") (pintype "output"))
      (node (ref "R10") (pin "1") (pinfunction "1_1") (pintype "passive"))
    )
    (net (code "64") (name "Net-(IC3C-+IN)") (class "Default")
      (node (ref "IC3") (pin "12") (pinfunction "+IN_12") (pintype "input"))
      (node (ref "JP104") (pin "1") (pinfunction "1_1") (pintype "passive"))
      (node (ref "R28") (pin "1") (pinfunction "1_1") (pintype "passive"))
    )
    (net (code "65") (name "Net-(IC3C--IN)") (class "Default")
      (node (ref "IC3") (pin "13") (pinfunction "-IN_13") (pintype "input"))
      (node (ref "IC3") (pin "14") (pinfunction "OUT_14") (pintype "output"))
      (node (ref "R12") (pin "1") (pinfunction "1_1") (pintype "passive"))
    )
    (net (code "66") (name "Net-(IC3D-+IN)") (class "Default")
      (node (ref "IC3") (pin "10") (pinfunction "+IN_10") (pintype "input"))
      (node (ref "JP105") (pin "1") (pinfunction "1_1") (pintype "passive"))
      (node (ref "R27") (pin "1") (pinfunction "1_1") (pintype "passive"))
    )
    (net (code "67") (name "Net-(IC3D--IN)") (class "Default")
      (node (ref "IC3") (pin "8") (pinfunction "OUT_8") (pintype "output"))
      (node (ref "IC3") (pin "9") (pinfunction "-IN_9") (pintype "input"))
      (node (ref "R11") (pin "1") (pinfunction "1_1") (pintype "passive"))
    )
    (net (code "68") (name "Net-(IC4A-+IN)") (class "Default")
      (node (ref "IC4") (pin "3") (pinfunction "+IN_3") (pintype "input"))
      (node (ref "JP103") (pin "1") (pinfunction "1_1") (pintype "passive"))
      (node (ref "R29") (pin "1") (pinfunction "1_1") (pintype "passive"))
    )
    (net (code "69") (name "Net-(IC4A--IN)") (class "Default")
      (node (ref "IC4") (pin "1") (pinfunction "OUT_1") (pintype "output"))
      (node (ref "IC4") (pin "2") (pinfunction "-IN_2") (pintype "input"))
      (node (ref "R13") (pin "1") (pinfunction "1_1") (pintype "passive"))
    )
    (net (code "70") (name "Net-(IC4B-+IN)") (class "Default")
      (node (ref "IC4") (pin "5") (pinfunction "+IN_5") (pintype "input"))
      (node (ref "JP102") (pin "1") (pinfunction "1_1") (pintype "passive"))
      (node (ref "R30") (pin "1") (pinfunction "1_1") (pintype "passive"))
    )
    (net (code "71") (name "Net-(IC4B--IN)") (class "Default")
      (node (ref "IC4") (pin "6") (pinfunction "-IN_6") (pintype "input"))
      (node (ref "IC4") (pin "7") (pinfunction "OUT_7") (pintype "output"))
      (node (ref "R14") (pin "1") (pinfunction "1_1") (pintype "passive"))
    )
    (net (code "72") (name "Net-(IC4C-+IN)") (class "Default")
      (node (ref "IC4") (pin "12") (pinfunction "+IN_12") (pintype "input"))
      (node (ref "JP100") (pin "1") (pinfunction "1_1") (pintype "passive"))
      (node (ref "R32") (pin "1") (pinfunction "1_1") (pintype "passive"))
    )
    (net (code "73") (name "Net-(IC4C--IN)") (class "Default")
      (node (ref "IC4") (pin "13") (pinfunction "-IN_13") (pintype "input"))
      (node (ref "IC4") (pin "14") (pinfunction "OUT_14") (pintype "output"))
      (node (ref "R16") (pin "1") (pinfunction "1_1") (pintype "passive"))
    )
    (net (code "74") (name "Net-(IC4D-+IN)") (class "Default")
      (node (ref "IC4") (pin "10") (pinfunction "+IN_10") (pintype "input"))
      (node (ref "JP101") (pin "1") (pinfunction "1_1") (pintype "passive"))
      (node (ref "R31") (pin "1") (pinfunction "1_1") (pintype "passive"))
    )
    (net (code "75") (name "Net-(IC4D--IN)") (class "Default")
      (node (ref "IC4") (pin "8") (pinfunction "OUT_8") (pintype "output"))
      (node (ref "IC4") (pin "9") (pinfunction "-IN_9") (pintype "input"))
      (node (ref "R15") (pin "1") (pinfunction "1_1") (pintype "passive"))
    )
    (net (code "76") (name "Net-(IC5A-+IN)") (class "Default")
      (node (ref "IC5") (pin "3") (pinfunction "+IN_3") (pintype "input"))
      (node (ref "R55") (pin "2") (pinfunction "2_2") (pintype "passive"))
      (node (ref "R56") (pin "2") (pinfunction "2_2") (pintype "passive"))
    )
    (net (code "77") (name "Net-(IC5B-+IN)") (class "Default")
      (node (ref "IC5") (pin "5") (pinfunction "+IN_5") (pintype "input"))
      (node (ref "R71") (pin "2") (pinfunction "2_2") (pintype "passive"))
      (node (ref "R72") (pin "2") (pinfunction "2_2") (pintype "passive"))
    )
    (net (code "78") (name "Net-(IC5C-+IN)") (class "Default")
      (node (ref "IC5") (pin "10") (pinfunction "+IN_10") (pintype "input"))
      (node (ref "R69") (pin "2") (pinfunction "2_2") (pintype "passive"))
      (node (ref "R70") (pin "2") (pinfunction "2_2") (pintype "passive"))
    )
    (net (code "79") (name "Net-(IC5D-+IN)") (class "Default")
      (node (ref "IC5") (pin "12") (pinfunction "+IN_12") (pintype "input"))
      (node (ref "R53") (pin "2") (pinfunction "2_2") (pintype "passive"))
      (node (ref "R54") (pin "2") (pinfunction "2_2") (pintype "passive"))
    )
    (net (code "80") (name "Net-(IC6A-+IN)") (class "Default")
      (node (ref "IC6") (pin "3") (pinfunction "+IN_3") (pintype "input"))
      (node (ref "R59") (pin "2") (pinfunction "2_2") (pintype "passive"))
      (node (ref "R60") (pin "2") (pinfunction "2_2") (pintype "passive"))
    )
    (net (code "81") (name "Net-(IC6B-+IN)") (class "Default")
      (node (ref "IC6") (pin "5") (pinfunction "+IN_5") (pintype "input"))
      (node (ref "R75") (pin "2") (pinfunction "2_2") (pintype "passive"))
      (node (ref "R76") (pin "2") (pinfunction "2_2") (pintype "passive"))
    )
    (net (code "82") (name "Net-(IC6C-+IN)") (class "Default")
      (node (ref "IC6") (pin "10") (pinfunction "+IN_10") (pintype "input"))
      (node (ref "R73") (pin "2") (pinfunction "2_2") (pintype "passive"))
      (node (ref "R74") (pin "2") (pinfunction "2_2") (pintype "passive"))
    )
    (net (code "83") (name "Net-(IC6D-+IN)") (class "Default")
      (node (ref "IC6") (pin "12") (pinfunction "+IN_12") (pintype "input"))
      (node (ref "R57") (pin "2") (pinfunction "2_2") (pintype "passive"))
      (node (ref "R58") (pin "2") (pinfunction "2_2") (pintype "passive"))
    )
    (net (code "84") (name "Net-(IC7A-+IN)") (class "Default")
      (node (ref "IC7") (pin "3") (pinfunction "+IN_3") (pintype "input"))
      (node (ref "R63") (pin "2") (pinfunction "2_2") (pintype "passive"))
      (node (ref "R64") (pin "2") (pinfunction "2_2") (pintype "passive"))
    )
    (net (code "85") (name "Net-(IC7B-+IN)") (class "Default")
      (node (ref "IC7") (pin "5") (pinfunction "+IN_5") (pintype "input"))
      (node (ref "R79") (pin "2") (pinfunction "2_2") (pintype "passive"))
      (node (ref "R80") (pin "2") (pinfunction "2_2") (pintype "passive"))
    )
    (net (code "86") (name "Net-(IC7C-+IN)") (class "Default")
      (node (ref "IC7") (pin "10") (pinfunction "+IN_10") (pintype "input"))
      (node (ref "R77") (pin "2") (pinfunction "2_2") (pintype "passive"))
      (node (ref "R78") (pin "2") (pinfunction "2_2") (pintype "passive"))
    )
    (net (code "87") (name "Net-(IC7D-+IN)") (class "Default")
      (node (ref "IC7") (pin "12") (pinfunction "+IN_12") (pintype "input"))
      (node (ref "R61") (pin "2") (pinfunction "2_2") (pintype "passive"))
      (node (ref "R62") (pin "2") (pinfunction "2_2") (pintype "passive"))
    )
    (net (code "88") (name "Net-(IC8A-+IN)") (class "Default")
      (node (ref "IC8") (pin "3") (pinfunction "+IN_3") (pintype "input"))
      (node (ref "R51") (pin "2") (pinfunction "2_2") (pintype "passive"))
      (node (ref "R52") (pin "2") (pinfunction "2_2") (pintype "passive"))
    )
    (net (code "89") (name "Net-(IC8B-+IN)") (class "Default")
      (node (ref "IC8") (pin "5") (pinfunction "+IN_5") (pintype "input"))
      (node (ref "R67") (pin "2") (pinfunction "2_2") (pintype "passive"))
      (node (ref "R68") (pin "2") (pinfunction "2_2") (pintype "passive"))
    )
    (net (code "90") (name "Net-(IC8C-+IN)") (class "Default")
      (node (ref "IC8") (pin "10") (pinfunction "+IN_10") (pintype "input"))
      (node (ref "R81") (pin "2") (pinfunction "2_2") (pintype "passive"))
      (node (ref "R82") (pin "2") (pinfunction "2_2") (pintype "passive"))
    )
    (net (code "91") (name "Net-(JP2-LEFT)") (class "Default")
      (node (ref "JP2") (pin "P$1_TIP") (pinfunction "LEFT_P$1_TIP") (pintype "bidirectional"))
      (node (ref "S100") (pin "P2") (pinfunction "5_P2") (pintype "bidirectional"))
    )
    (net (code "92") (name "Net-(JP2-RIGHT)") (class "Default")
      (node (ref "JP2") (pin "P$2_SWITCH") (pinfunction "RIGHT_P$2_SWITCH") (pintype "bidirectional"))
      (node (ref "S100") (pin "P1") (pinfunction "2_P1") (pintype "bidirectional"))
    )
    (net (code "93") (name "Net-(JP100-Pad2)") (class "Default")
      (node (ref "JP100") (pin "2") (pinfunction "2_2") (pintype "passive"))
      (node (ref "R48") (pin "1") (pinfunction "1_1") (pintype "passive"))
    )
    (net (code "94") (name "Net-(JP101-Pad2)") (class "Default")
      (node (ref "JP101") (pin "2") (pinfunction "2_2") (pintype "passive"))
      (node (ref "R47") (pin "1") (pinfunction "1_1") (pintype "passive"))
    )
    (net (code "95") (name "Net-(JP102-Pad2)") (class "Default")
      (node (ref "JP102") (pin "2") (pinfunction "2_2") (pintype "passive"))
      (node (ref "R46") (pin "1") (pinfunction "1_1") (pintype "passive"))
    )
    (net (code "96") (name "Net-(JP103-Pad2)") (class "Default")
      (node (ref "JP103") (pin "2") (pinfunction "2_2") (pintype "passive"))
      (node (ref "R45") (pin "1") (pinfunction "1_1") (pintype "passive"))
    )
    (net (code "97") (name "Net-(JP104-Pad2)") (class "Default")
      (node (ref "JP104") (pin "2") (pinfunction "2_2") (pintype "passive"))
      (node (ref "R44") (pin "1") (pinfunction "1_1") (pintype "passive"))
    )
    (net (code "98") (name "Net-(JP105-Pad2)") (class "Default")
      (node (ref "JP105") (pin "2") (pinfunction "2_2") (pintype "passive"))
      (node (ref "R43") (pin "1") (pinfunction "1_1") (pintype "passive"))
    )
    (net (code "99") (name "Net-(JP106-Pad2)") (class "Default")
      (node (ref "JP106") (pin "2") (pinfunction "2_2") (pintype "passive"))
      (node (ref "R42") (pin "1") (pinfunction "1_1") (pintype "passive"))
    )
    (net (code "100") (name "Net-(JP107-Pad2)") (class "Default")
      (node (ref "JP107") (pin "2") (pinfunction "2_2") (pintype "passive"))
      (node (ref "R41") (pin "1") (pinfunction "1_1") (pintype "passive"))
    )
    (net (code "101") (name "Net-(JP108-Pad2)") (class "Default")
      (node (ref "JP108") (pin "2") (pinfunction "2_2") (pintype "passive"))
      (node (ref "R40") (pin "1") (pinfunction "1_1") (pintype "passive"))
    )
    (net (code "102") (name "Net-(JP109-Pad2)") (class "Default")
      (node (ref "JP109") (pin "2") (pinfunction "2_2") (pintype "passive"))
      (node (ref "R39") (pin "1") (pinfunction "1_1") (pintype "passive"))
    )
    (net (code "103") (name "Net-(JP110-Pad2)") (class "Default")
      (node (ref "JP110") (pin "2") (pinfunction "2_2") (pintype "passive"))
      (node (ref "R38") (pin "1") (pinfunction "1_1") (pintype "passive"))
    )
    (net (code "104") (name "Net-(JP111-Pad2)") (class "Default")
      (node (ref "JP111") (pin "2") (pinfunction "2_2") (pintype "passive"))
      (node (ref "R37") (pin "1") (pinfunction "1_1") (pintype "passive"))
    )
    (net (code "105") (name "Net-(JP112-Pad2)") (class "Default")
      (node (ref "JP112") (pin "2") (pinfunction "2_2") (pintype "passive"))
      (node (ref "R36") (pin "1") (pinfunction "1_1") (pintype "passive"))
    )
    (net (code "106") (name "Net-(JP113-Pad2)") (class "Default")
      (node (ref "JP113") (pin "2") (pinfunction "2_2") (pintype "passive"))
      (node (ref "R35") (pin "1") (pinfunction "1_1") (pintype "passive"))
    )
    (net (code "107") (name "Net-(JP114-Pad2)") (class "Default")
      (node (ref "JP114") (pin "2") (pinfunction "2_2") (pintype "passive"))
      (node (ref "R34") (pin "1") (pinfunction "1_1") (pintype "passive"))
    )
    (net (code "108") (name "Net-(JP115-Pad2)") (class "Default")
      (node (ref "JP115") (pin "2") (pinfunction "2_2") (pintype "passive"))
      (node (ref "R33") (pin "1") (pinfunction "1_1") (pintype "passive"))
    )
    (net (code "109") (name "Net-(LED1-PadA)") (class "Default")
      (node (ref "LED1") (pin "A") (pinfunction "A_A") (pintype "passive"))
      (node (ref "R84") (pin "1") (pinfunction "1_1") (pintype "passive"))
    )
    (net (code "110") (name "Net-(S100-1)") (class "Default")
      (node (ref "R85") (pin "1") (pinfunction "1_1") (pintype "passive"))
      (node (ref "S100") (pin "P1-TA") (pinfunction "1_P1-TA") (pintype "bidirectional"))
      (node (ref "S100") (pin "P2-TB") (pinfunction "6_P2-TB") (pintype "bidirectional"))
    )
    (net (code "111") (name "Net-(S100-3)") (class "Default")
      (node (ref "R83") (pin "1") (pinfunction "1_1") (pintype "passive"))
      (node (ref "S100") (pin "P1-TB") (pinfunction "3_P1-TB") (pintype "bidirectional"))
      (node (ref "S100") (pin "P2-TA") (pinfunction "4_P2-TA") (pintype "bidirectional"))
    )
    (net (code "112") (name "Net-(V1-BYPASS)") (class "Default")
      (node (ref "C3") (pin "1") (pinfunction "1_1") (pintype "passive"))
      (node (ref "V1") (pin "4") (pinfunction "BYPASS_4") (pintype "passive"))
    )
    (net (code "113") (name "S$2") (class "Default")
      (node (ref "IC8") (pin "12") (pinfunction "+IN_12") (pintype "input"))
      (node (ref "R65") (pin "2") (pinfunction "2_2") (pintype "passive"))
      (node (ref "R66") (pin "2") (pinfunction "2_2") (pintype "passive"))
    )
    (net (code "114") (name "S0") (class "Default")
      (node (ref "IC10") (pin "8") (pinfunction "8/TX3_8") (pintype "bidirectional"))
      (node (ref "IC9") (pin "10") (pinfunction "S0_10") (pintype "input"))
    )
    (net (code "115") (name "S1") (class "Default")
      (node (ref "IC10") (pin "7") (pinfunction "7/RX3_7") (pintype "bidirectional"))
      (node (ref "IC9") (pin "11") (pinfunction "S1_11") (pintype "input"))
    )
    (net (code "116") (name "S2") (class "Default")
      (node (ref "IC10") (pin "6") (pinfunction "6/PWM_6") (pintype "bidirectional"))
      (node (ref "IC9") (pin "14") (pinfunction "S2_14") (pintype "input"))
    )
    (net (code "117") (name "S3") (class "Default")
      (node (ref "IC10") (pin "5") (pinfunction "5/PWM_5") (pintype "bidirectional"))
      (node (ref "IC9") (pin "13") (pinfunction "S3_13") (pintype "input"))
    )
    (net (code "118") (name "SCL") (class "Default")
      (node (ref "D2") (pin "A") (pinfunction "A_A") (pintype "passive"))
      (node (ref "D3") (pin "C") (pinfunction "C_C") (pintype "passive"))
      (node (ref "I2C") (pin "2") (pinfunction "2_2") (pintype "passive"))
      (node (ref "IC10") (pin "19/A5") (pinfunction "19/A5/T/SCL0_19/A5") (pintype "bidirectional"))
      (node (ref "JP1") (pin "P$2_SWITCH") (pinfunction "RIGHT_P$2_SWITCH") (pintype "bidirectional"))
      (node (ref "R49") (pin "1") (pinfunction "1_1") (pintype "passive"))
    )
    (net (code "119") (name "SDA") (class "Default")
      (node (ref "D4") (pin "C") (pinfunction "C_C") (pintype "passive"))
      (node (ref "D5") (pin "A") (pinfunction "A_A") (pintype "passive"))
      (node (ref "I2C") (pin "1") (pinfunction "1_1") (pintype "passive"))
      (node (ref "IC10") (pin "18/A4") (pinfunction "18/A4/T/SDA0_18/A4") (pintype "bidirectional"))
      (node (ref "JP1") (pin "P$1_TIP") (pinfunction "LEFT_P$1_TIP") (pintype "bidirectional"))
      (node (ref "R50") (pin "1") (pinfunction "1_1") (pintype "passive"))
    )
    (net (code "120") (name "W0") (class "Default")
      (node (ref "R17") (pin "2") (pinfunction "2_2") (pintype "passive"))
      (node (ref "R69") (pin "1") (pinfunction "1_1") (pintype "passive"))
      (node (ref "U$1") (pin "WIPER") (pinfunction "2_WIPER") (pintype "bidirectional"))
    )
    (net (code "121") (name "W1") (class "Default")
      (node (ref "R18") (pin "2") (pinfunction "2_2") (pintype "passive"))
      (node (ref "R53") (pin "1") (pinfunction "1_1") (pintype "passive"))
      (node (ref "U$2") (pin "WIPER") (pinfunction "2_WIPER") (pintype "bidirectional"))
    )
    (net (code "122") (name "W2") (class "Default")
      (node (ref "R19") (pin "2") (pinfunction "2_2") (pintype "passive"))
      (node (ref "R71") (pin "1") (pinfunction "1_1") (pintype "passive"))
      (node (ref "U$3") (pin "WIPER") (pinfunction "2_WIPER") (pintype "bidirectional"))
    )
    (net (code "123") (name "W3") (class "Default")
      (node (ref "R20") (pin "2") (pinfunction "2_2") (pintype "passive"))
      (node (ref "R55") (pin "1") (pinfunction "1_1") (pintype "passive"))
      (node (ref "U$4") (pin "WIPER") (pinfunction "2_WIPER") (pintype "bidirectional"))
    )
    (net (code "124") (name "W4") (class "Default")
      (node (ref "R21") (pin "2") (pinfunction "2_2") (pintype "passive"))
      (node (ref "R73") (pin "1") (pinfunction "1_1") (pintype "passive"))
      (node (ref "U$5") (pin "WIPER") (pinfunction "2_WIPER") (pintype "bidirectional"))
    )
    (net (code "125") (name "W5") (class "Default")
      (node (ref "R22") (pin "2") (pinfunction "2_2") (pintype "passive"))
      (node (ref "R57") (pin "1") (pinfunction "1_1") (pintype "passive"))
      (node (ref "U$6") (pin "WIPER") (pinfunction "2_WIPER") (pintype "bidirectional"))
    )
    (net (code "126") (name "W6") (class "Default")
      (node (ref "R23") (pin "2") (pinfunction "2_2") (pintype "passive"))
      (node (ref "R75") (pin "1") (pinfunction "1_1") (pintype "passive"))
      (node (ref "U$7") (pin "WIPER") (pinfunction "2_WIPER") (pintype "bidirectional"))
    )
    (net (code "127") (name "W7") (class "Default")
      (node (ref "R24") (pin "2") (pinfunction "2_2") (pintype "passive"))
      (node (ref "R59") (pin "1") (pinfunction "1_1") (pintype "passive"))
      (node (ref "U$8") (pin "WIPER") (pinfunction "2_WIPER") (pintype "bidirectional"))
    )
    (net (code "128") (name "W8") (class "Default")
      (node (ref "R25") (pin "2") (pinfunction "2_2") (pintype "passive"))
      (node (ref "R77") (pin "1") (pinfunction "1_1") (pintype "passive"))
      (node (ref "U$9") (pin "WIPER") (pinfunction "2_WIPER") (pintype "bidirectional"))
    )
    (net (code "129") (name "W9") (class "Default")
      (node (ref "R26") (pin "2") (pinfunction "2_2") (pintype "passive"))
      (node (ref "R61") (pin "1") (pinfunction "1_1") (pintype "passive"))
      (node (ref "U$10") (pin "WIPER") (pinfunction "2_WIPER") (pintype "bidirectional"))
    )
    (net (code "130") (name "W10") (class "Default")
      (node (ref "R27") (pin "2") (pinfunction "2_2") (pintype "passive"))
      (node (ref "R79") (pin "1") (pinfunction "1_1") (pintype "passive"))
      (node (ref "U$11") (pin "WIPER") (pinfunction "2_WIPER") (pintype "bidirectional"))
    )
    (net (code "131") (name "W11") (class "Default")
      (node (ref "R28") (pin "2") (pinfunction "2_2") (pintype "passive"))
      (node (ref "R63") (pin "1") (pinfunction "1_1") (pintype "passive"))
      (node (ref "U$12") (pin "WIPER") (pinfunction "2_WIPER") (pintype "bidirectional"))
    )
    (net (code "132") (name "W12") (class "Default")
      (node (ref "R29") (pin "2") (pinfunction "2_2") (pintype "passive"))
      (node (ref "R81") (pin "1") (pinfunction "1_1") (pintype "passive"))
      (node (ref "U$13") (pin "WIPER") (pinfunction "2_WIPER") (pintype "bidirectional"))
    )
    (net (code "133") (name "W13") (class "Default")
      (node (ref "R30") (pin "2") (pinfunction "2_2") (pintype "passive"))
      (node (ref "R65") (pin "1") (pinfunction "1_1") (pintype "passive"))
      (node (ref "U$14") (pin "WIPER") (pinfunction "2_WIPER") (pintype "bidirectional"))
    )
    (net (code "134") (name "W14") (class "Default")
      (node (ref "R31") (pin "2") (pinfunction "2_2") (pintype "passive"))
      (node (ref "R67") (pin "1") (pinfunction "1_1") (pintype "passive"))
      (node (ref "U$15") (pin "WIPER") (pinfunction "2_WIPER") (pintype "bidirectional"))
    )
    (net (code "135") (name "W15") (class "Default")
      (node (ref "R32") (pin "2") (pinfunction "2_2") (pintype "passive"))
      (node (ref "R51") (pin "1") (pinfunction "1_1") (pintype "passive"))
      (node (ref "U$16") (pin "WIPER") (pinfunction "2_WIPER") (pintype "bidirectional"))
    )
    (net (code "136") (name "unconnected-(IC10-0{slash}RX1{slash}T-Pad0)") (class "Default")
      (node (ref "IC10") (pin "0") (pinfunction "0/RX1/T_0") (pintype "bidirectional"))
    )
    (net (code "137") (name "unconnected-(IC10-3{slash}CAN-TX{slash}PWM-Pad3)") (class "Default")
      (node (ref "IC10") (pin "3") (pinfunction "3/CAN-TX/PWM_3") (pintype "bidirectional"))
    )
    (net (code "138") (name "unconnected-(IC10-4{slash}CAN-RX{slash}PWM-Pad4)") (class "Default")
      (node (ref "IC10") (pin "4") (pinfunction "4/CAN-RX/PWM_4") (pintype "bidirectional"))
    )
    (net (code "139") (name "unconnected-(IC10-9{slash}RX2{slash}PWM-Pad9)") (class "Default")
      (node (ref "IC10") (pin "9") (pinfunction "9/RX2/PWM_9") (pintype "bidirectional"))
    )
    (net (code "140") (name "unconnected-(IC10-10{slash}TX2{slash}PWM-Pad10)") (class "Default")
      (node (ref "IC10") (pin "10") (pinfunction "10/TX2/PWM_10") (pintype "bidirectional"))
    )
    (net (code "141") (name "unconnected-(IC10-11{slash}MOSI-Pad11)") (class "Default")
      (node (ref "IC10") (pin "11") (pinfunction "11/MOSI_11") (pintype "bidirectional"))
    )
    (net (code "142") (name "unconnected-(IC10-12{slash}MISO-Pad12)") (class "Default")
      (node (ref "IC10") (pin "12") (pinfunction "12/MISO_12") (pintype "bidirectional"))
    )
    (net (code "143") (name "unconnected-(IC10-13{slash}SCK{slash}LED-Pad13)") (class "Default")
      (node (ref "IC10") (pin "13") (pinfunction "13/SCK/LED_13") (pintype "bidirectional"))
    )
    (net (code "144") (name "unconnected-(IC10-15{slash}A1{slash}T-Pad15{slash}A1)") (class "Default")
      (node (ref "IC10") (pin "15/A1") (pinfunction "15/A1/T_15/A1") (pintype "bidirectional"))
    )
    (net (code "145") (name "unconnected-(IC10-16{slash}A2{slash}T-Pad16{slash}A2)") (class "Default")
      (node (ref "IC10") (pin "16/A2") (pinfunction "16/A2/T_16/A2") (pintype "bidirectional"))
    )
    (net (code "146") (name "unconnected-(IC10-17{slash}A3{slash}T-Pad17{slash}A3)") (class "Default")
      (node (ref "IC10") (pin "17/A3") (pinfunction "17/A3/T_17/A3") (pintype "bidirectional"))
    )
    (net (code "147") (name "unconnected-(IC10-20{slash}A6{slash}PWM-Pad20{slash}A6)") (class "Default")
      (node (ref "IC10") (pin "20/A6") (pinfunction "20/A6/PWM_20/A6") (pintype "bidirectional"))
    )
    (net (code "148") (name "unconnected-(IC10-21{slash}A7{slash}PWM-Pad21{slash}A7)") (class "Default")
      (node (ref "IC10") (pin "21/A7") (pinfunction "21/A7/PWM_21/A7") (pintype "bidirectional"))
    )
    (net (code "149") (name "unconnected-(IC10-22{slash}A8{slash}T{slash}PWM-Pad22{slash}A8)") (class "Default")
      (node (ref "IC10") (pin "22/A8") (pinfunction "22/A8/T/PWM_22/A8") (pintype "bidirectional"))
    )
    (net (code "150") (name "unconnected-(IC10-23{slash}A9{slash}T{slash}PWM-Pad23{slash}A9)") (class "Default")
      (node (ref "IC10") (pin "23/A9") (pinfunction "23/A9/T/PWM_23/A9") (pintype "bidirectional"))
    )
    (net (code "151") (name "unconnected-(IC10-Pad2)") (class "Default")
      (node (ref "IC10") (pin "2") (pinfunction "2_2") (pintype "bidirectional"))
    )
    (net (code "152") (name "unconnected-(J1-SWITCH-PadP$2_SWITCH)") (class "Default")
      (node (ref "J1") (pin "P$2_SWITCH") (pinfunction "SWITCH_P$2_SWITCH") (pintype "passive"))
    )
    (net (code "153") (name "unconnected-(J2-SWITCH-PadP$2_SWITCH)") (class "Default")
      (node (ref "J2") (pin "P$2_SWITCH") (pinfunction "SWITCH_P$2_SWITCH") (pintype "passive"))
    )
    (net (code "154") (name "unconnected-(J3-SWITCH-PadP$2_SWITCH)") (class "Default")
      (node (ref "J3") (pin "P$2_SWITCH") (pinfunction "SWITCH_P$2_SWITCH") (pintype "passive"))
    )
    (net (code "155") (name "unconnected-(J4-SWITCH-PadP$2_SWITCH)") (class "Default")
      (node (ref "J4") (pin "P$2_SWITCH") (pinfunction "SWITCH_P$2_SWITCH") (pintype "passive"))
    )
    (net (code "156") (name "unconnected-(J5-SWITCH-PadP$2_SWITCH)") (class "Default")
      (node (ref "J5") (pin "P$2_SWITCH") (pinfunction "SWITCH_P$2_SWITCH") (pintype "passive"))
    )
    (net (code "157") (name "unconnected-(J6-SWITCH-PadP$2_SWITCH)") (class "Default")
      (node (ref "J6") (pin "P$2_SWITCH") (pinfunction "SWITCH_P$2_SWITCH") (pintype "passive"))
    )
    (net (code "158") (name "unconnected-(J7-SWITCH-PadP$2_SWITCH)") (class "Default")
      (node (ref "J7") (pin "P$2_SWITCH") (pinfunction "SWITCH_P$2_SWITCH") (pintype "passive"))
    )
    (net (code "159") (name "unconnected-(J8-SWITCH-PadP$2_SWITCH)") (class "Default")
      (node (ref "J8") (pin "P$2_SWITCH") (pinfunction "SWITCH_P$2_SWITCH") (pintype "passive"))
    )
    (net (code "160") (name "unconnected-(J9-SWITCH-PadP$2_SWITCH)") (class "Default")
      (node (ref "J9") (pin "P$2_SWITCH") (pinfunction "SWITCH_P$2_SWITCH") (pintype "passive"))
    )
    (net (code "161") (name "unconnected-(J10-SWITCH-PadP$2_SWITCH)") (class "Default")
      (node (ref "J10") (pin "P$2_SWITCH") (pinfunction "SWITCH_P$2_SWITCH") (pintype "passive"))
    )
    (net (code "162") (name "unconnected-(J11-SWITCH-PadP$2_SWITCH)") (class "Default")
      (node (ref "J11") (pin "P$2_SWITCH") (pinfunction "SWITCH_P$2_SWITCH") (pintype "passive"))
    )
    (net (code "163") (name "unconnected-(J12-SWITCH-PadP$2_SWITCH)") (class "Default")
      (node (ref "J12") (pin "P$2_SWITCH") (pinfunction "SWITCH_P$2_SWITCH") (pintype "passive"))
    )
    (net (code "164") (name "unconnected-(J13-SWITCH-PadP$2_SWITCH)") (class "Default")
      (node (ref "J13") (pin "P$2_SWITCH") (pinfunction "SWITCH_P$2_SWITCH") (pintype "passive"))
    )
    (net (code "165") (name "unconnected-(J14-SWITCH-PadP$2_SWITCH)") (class "Default")
      (node (ref "J14") (pin "P$2_SWITCH") (pinfunction "SWITCH_P$2_SWITCH") (pintype "passive"))
    )
    (net (code "166") (name "unconnected-(J15-SWITCH-PadP$2_SWITCH)") (class "Default")
      (node (ref "J15") (pin "P$2_SWITCH") (pinfunction "SWITCH_P$2_SWITCH") (pintype "passive"))
    )
    (net (code "167") (name "unconnected-(J16-SWITCH-PadP$2_SWITCH)") (class "Default")
      (node (ref "J16") (pin "P$2_SWITCH") (pinfunction "SWITCH_P$2_SWITCH") (pintype "passive"))
    )
    (net (code "168") (name "unconnected-(S101-3-PadP1-TB)") (class "Default")
      (node (ref "S101") (pin "P1-TB") (pinfunction "3_P1-TB") (pintype "bidirectional"))
    )
    (net (code "169") (name "unconnected-(SV100-Pad1)") (class "Default")
      (node (ref "SV100") (pin "1") (pinfunction "1_1") (pintype "passive"))
    )
    (net (code "170") (name "unconnected-(SV100-Pad2)") (class "Default")
      (node (ref "SV100") (pin "2") (pinfunction "2_2") (pintype "passive"))
    )
  )
)
